# throughhole_xbee.net
KiCad netlist of a schematic drawn in EAGLE
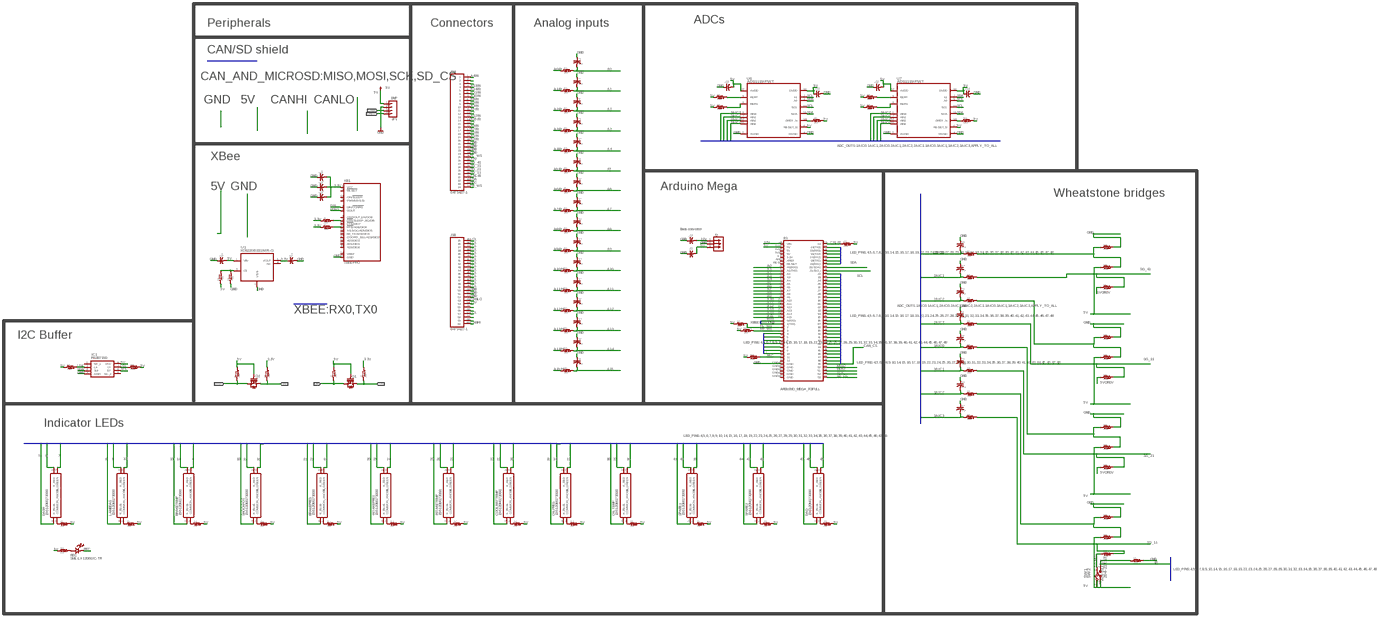
[diagram p0: schematic, sheet 1, overview]
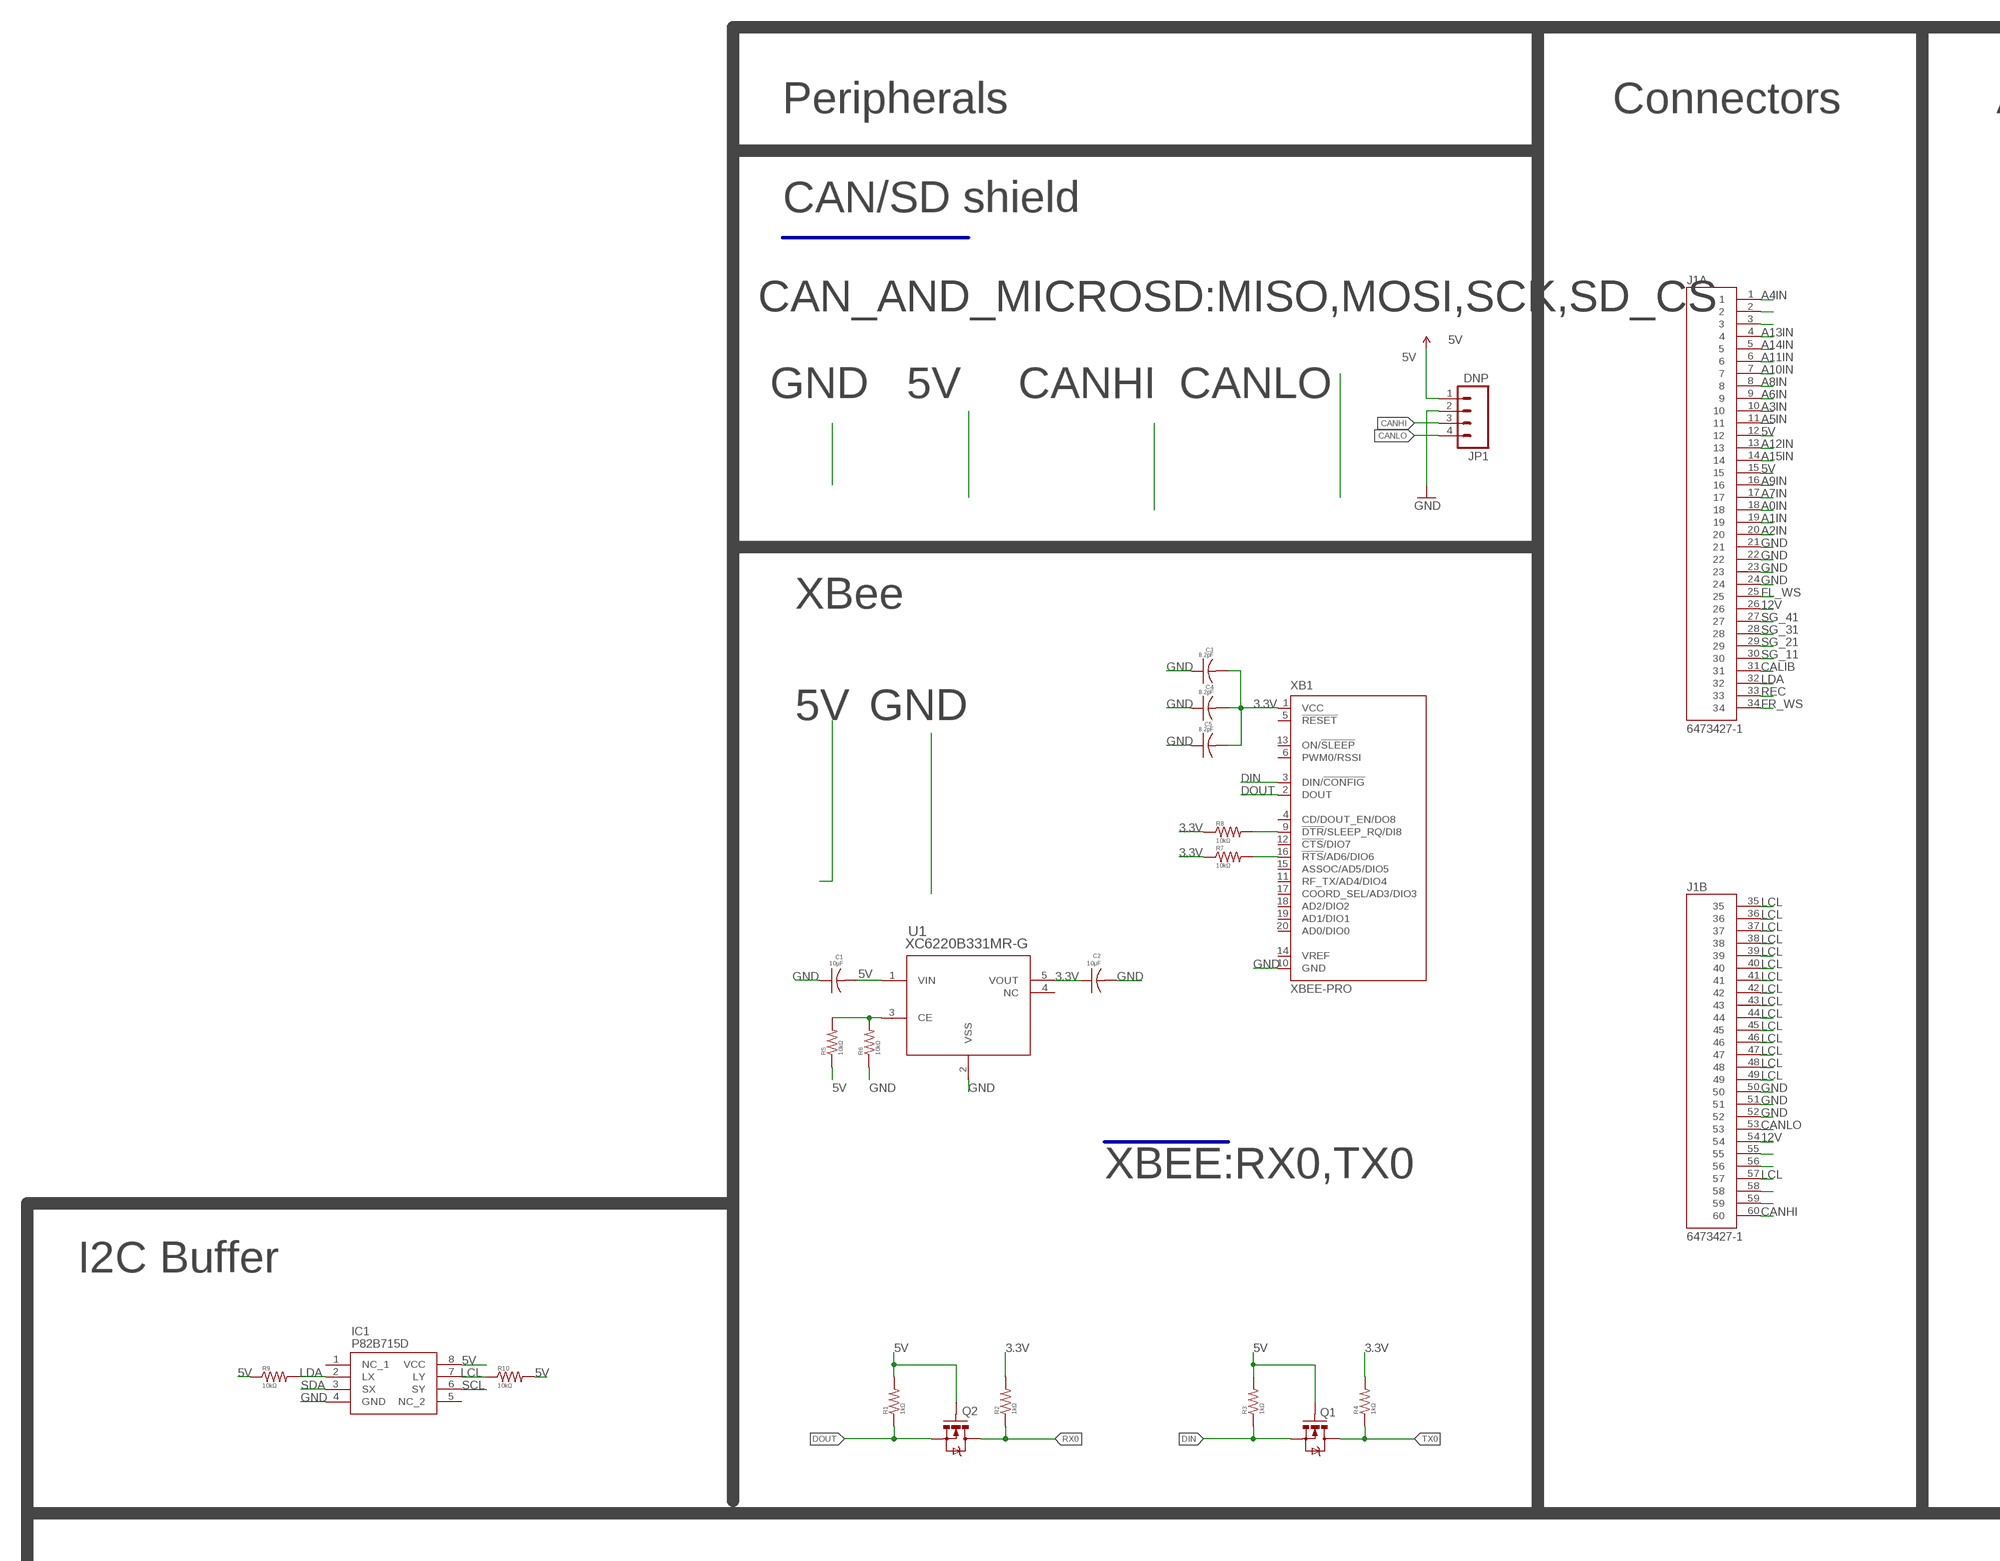
[diagram p1: schematic, sheet 1, part 1 of 5]
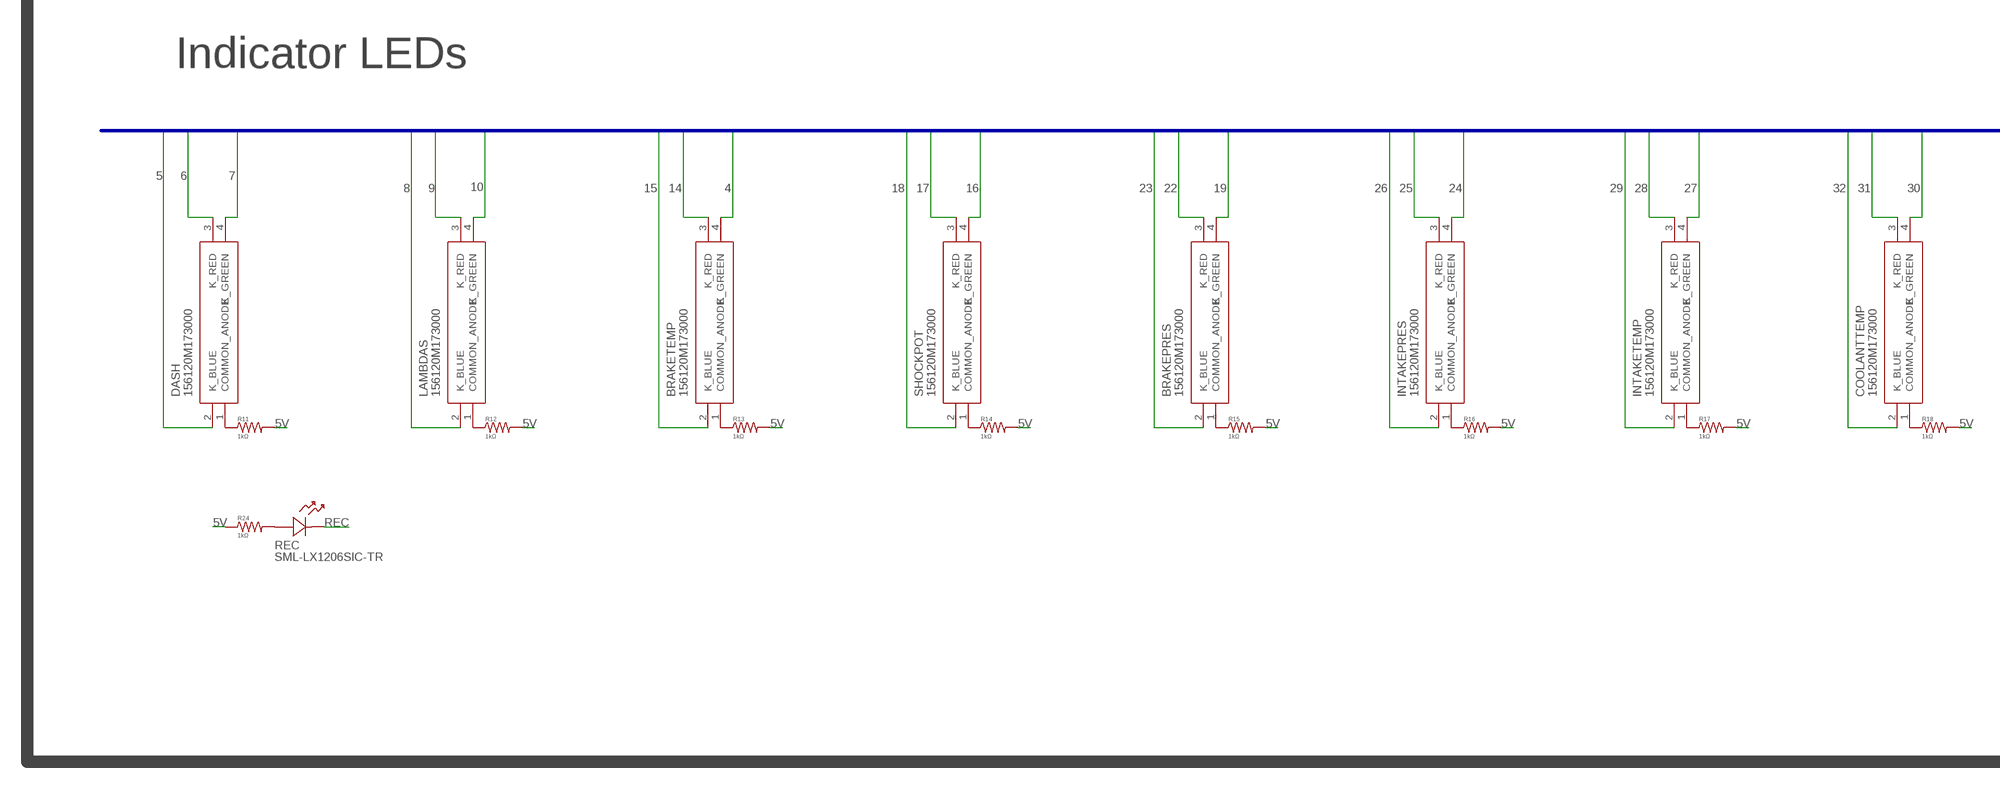
[diagram p2: schematic, sheet 1, part 2 of 5]
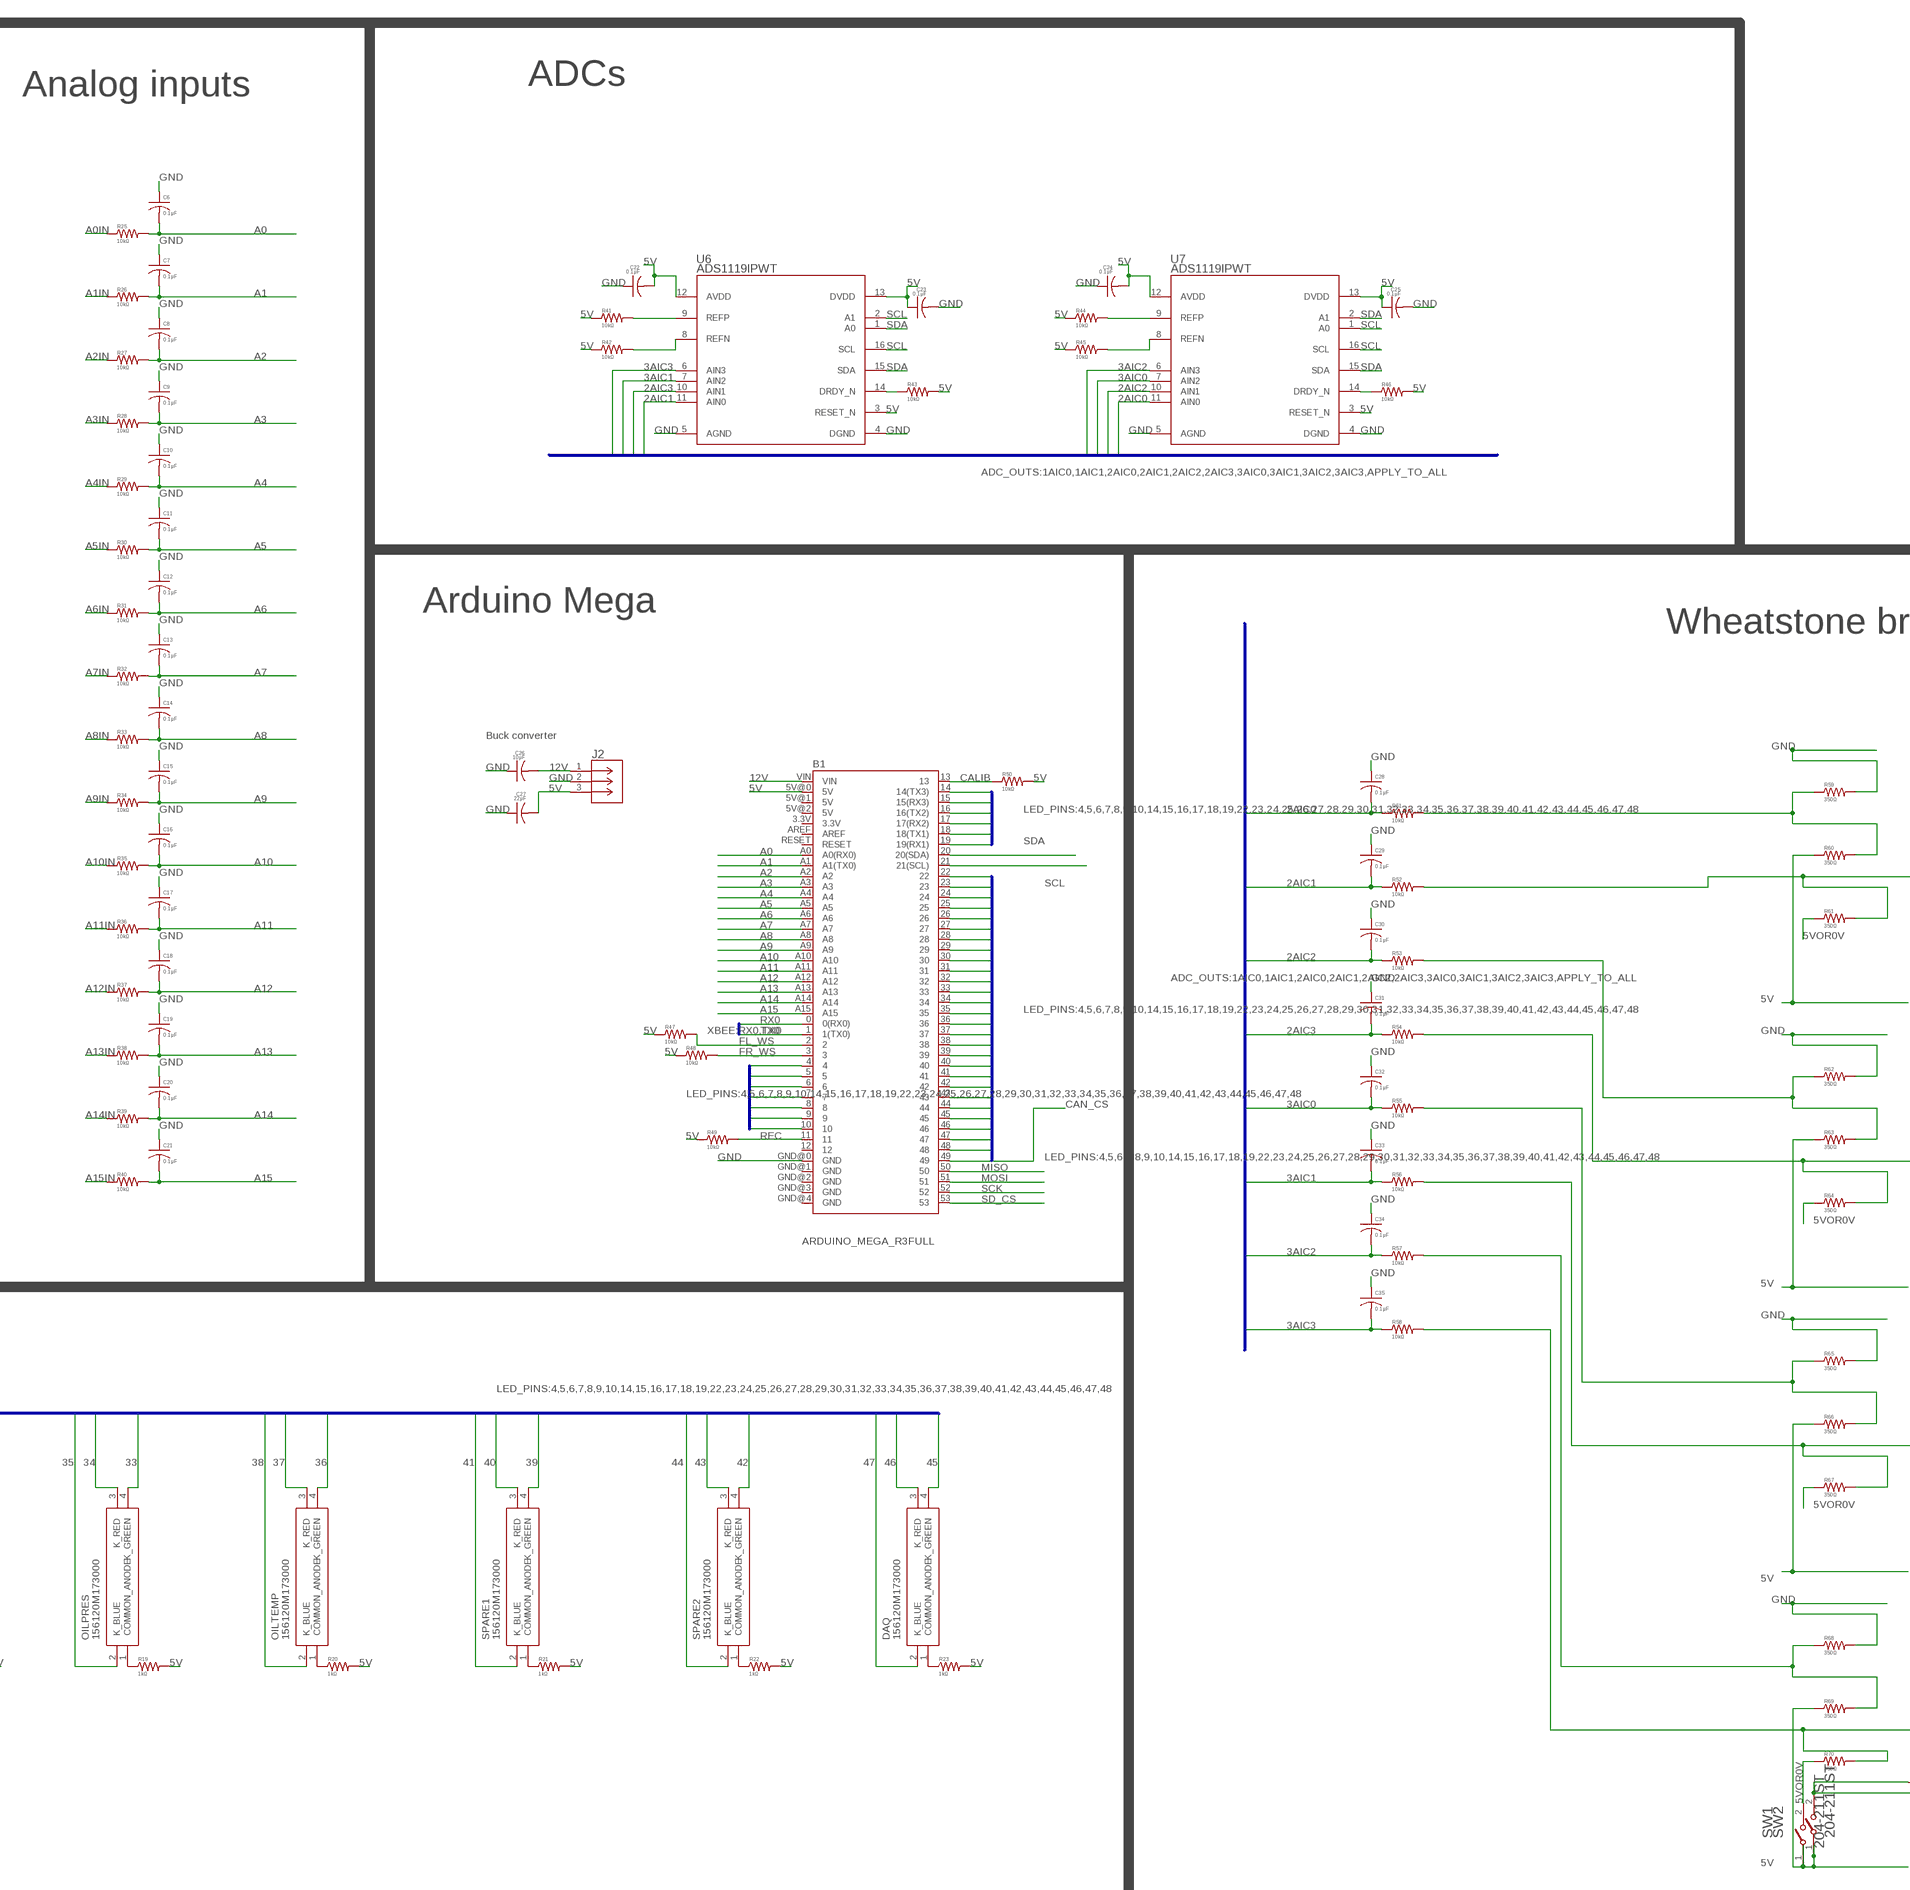
[diagram p3: schematic, sheet 1, part 3 of 5]
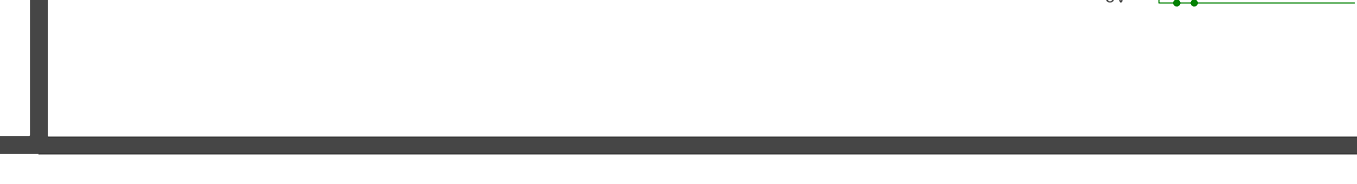
[diagram p4: schematic, sheet 1, part 4 of 5]
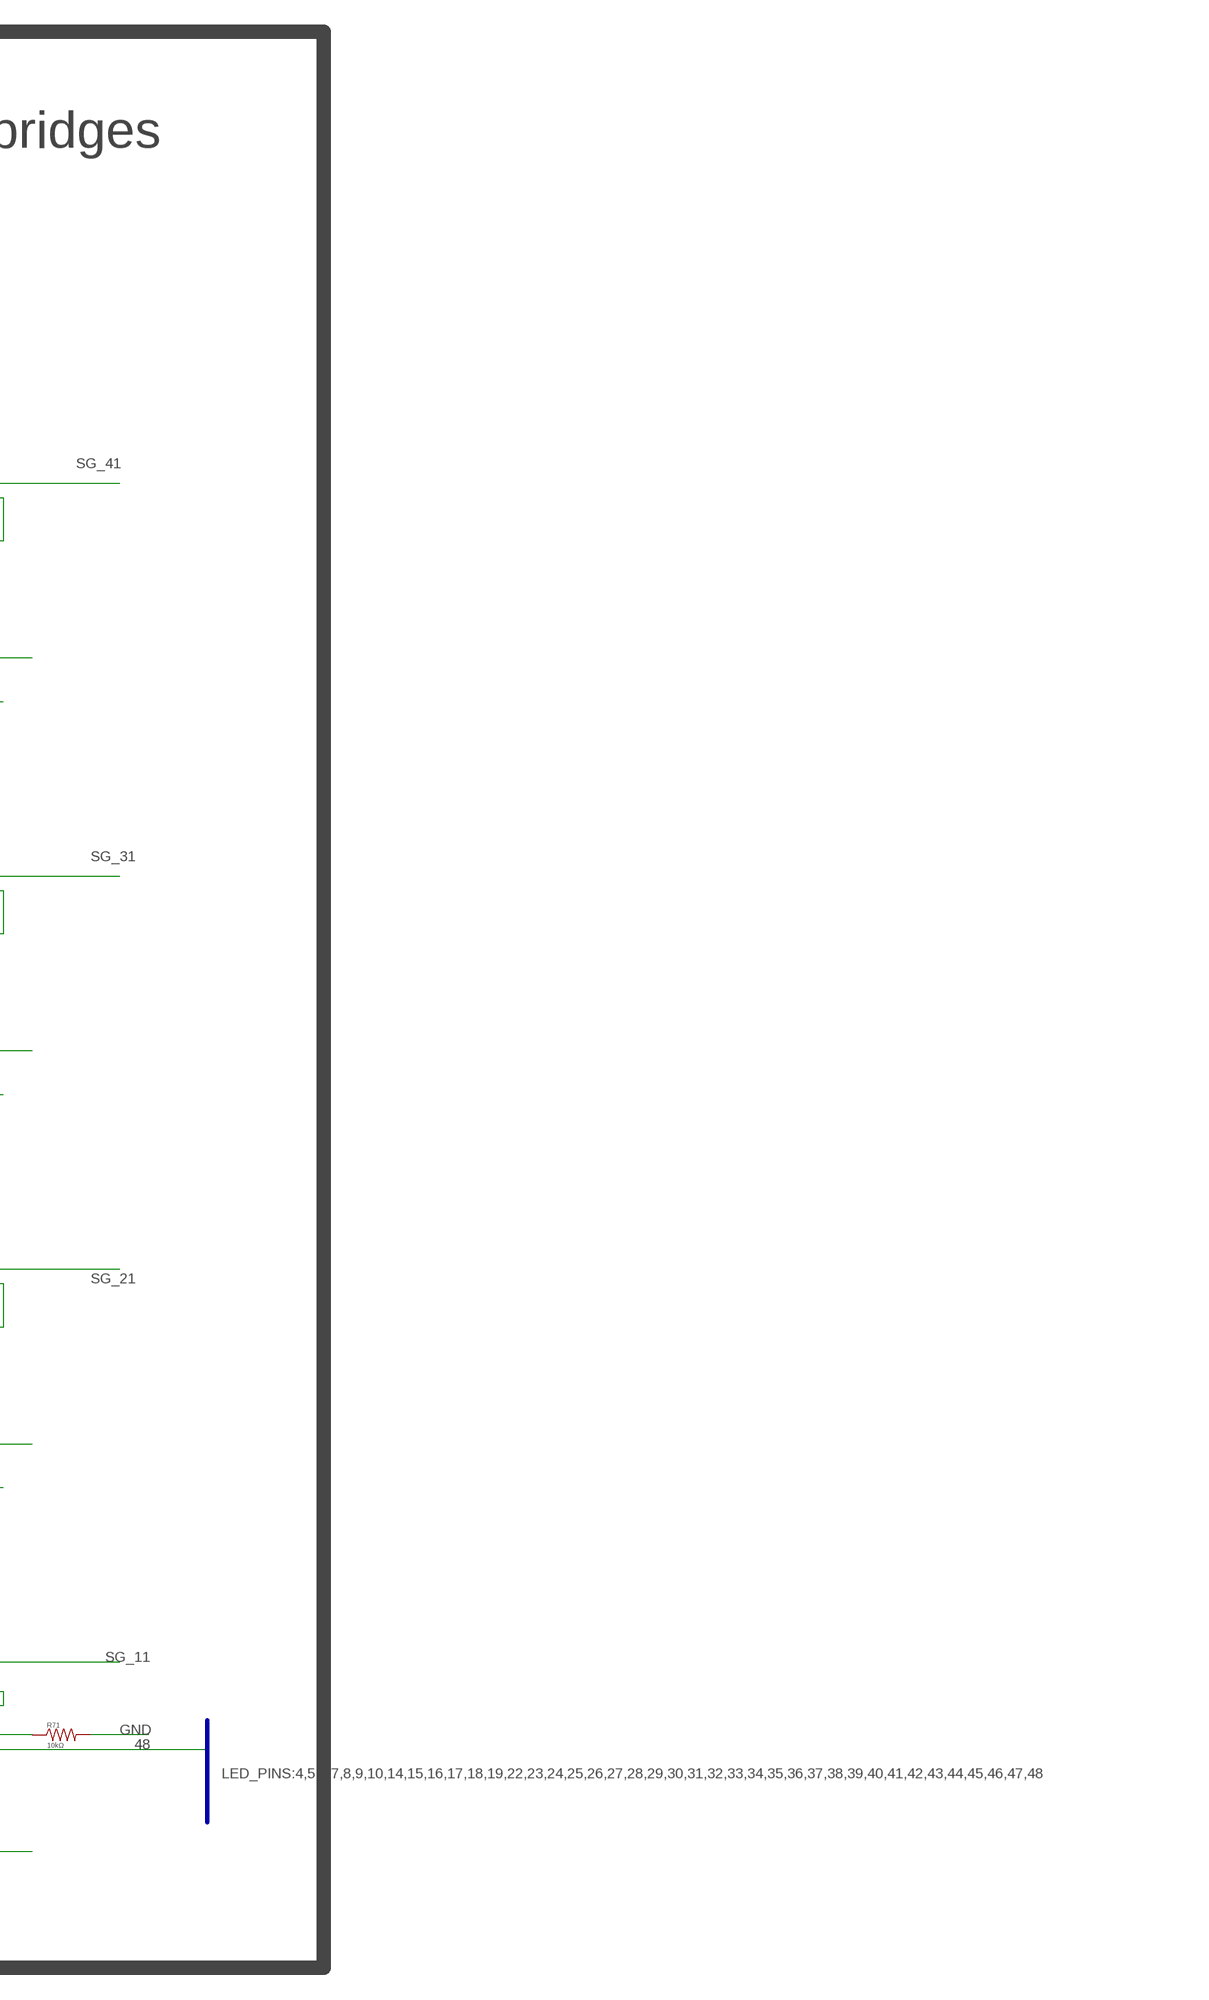
[diagram p5: schematic, sheet 1, part 5 of 5]
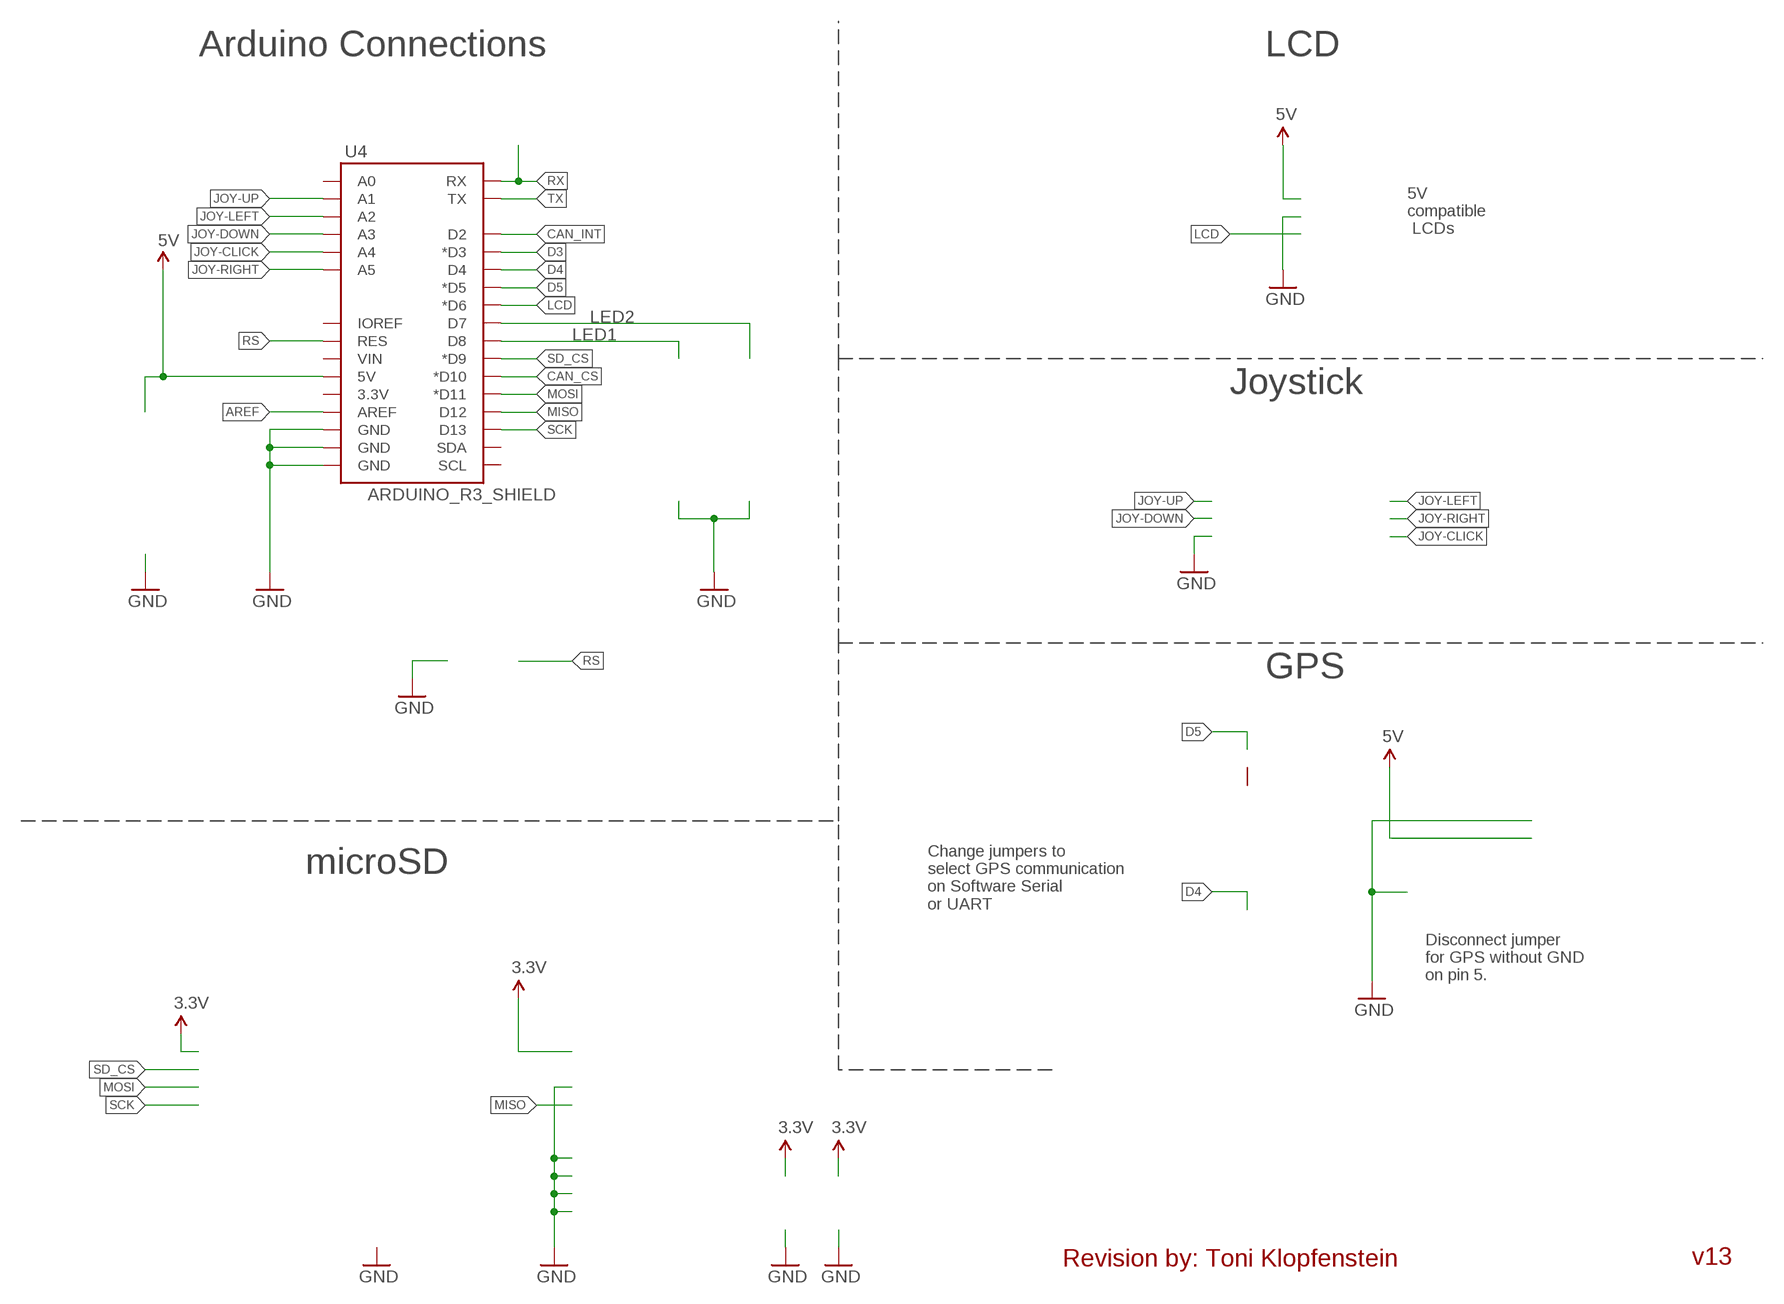
[diagram p6: schematic, sheet 2]

(export (version "E")
  (design (tool "Eeschema 10.0.6"))
  (components
    (comp (ref "U4")
      (value "ARDUINO_R3_SHIELD")
      (footprint "eagle-import:UNO_R3_SHIELD")
      (libsource (lib "eagle-import") (part "ARDUINO_R3_SHIELD"))
    )
    (comp (ref "B1")
      (value "ARDUINO_MEGA_R3FULL")
      (footprint "eagle-import:ARDUINO_MEGA")
      (libsource (lib "eagle-import") (part "ARDUINO_MEGA_R3FULL"))
    )
    (comp (ref "BRAKEPRES")
      (value "156120M173000")
      (footprint "eagle-import:156120M173000")
      (fields (field (name "MOUSER_PART_NUMBER") "710-156120M173000"))
      (libsource (lib "eagle-import") (part "156120M173000"))
    )
    (comp (ref "BRAKETEMP")
      (value "156120M173000")
      (footprint "eagle-import:156120M173000")
      (fields (field (name "MOUSER_PART_NUMBER") "710-156120M173000"))
      (libsource (lib "eagle-import") (part "156120M173000"))
    )
    (comp (ref "C1")
      (value "10μF")
      (footprint "eagle-import:C1206")
      (libsource (lib "eagle-import") (part "C-USC1206"))
    )
    (comp (ref "C2")
      (value "10μF")
      (footprint "eagle-import:C1206")
      (libsource (lib "eagle-import") (part "C-USC1206"))
    )
    (comp (ref "C3")
      (value "8.2pF")
      (footprint "eagle-import:C1206")
      (libsource (lib "eagle-import") (part "C-USC1206"))
    )
    (comp (ref "C4")
      (value "8.2pF")
      (footprint "eagle-import:C1206")
      (libsource (lib "eagle-import") (part "C-USC1206"))
    )
    (comp (ref "C5")
      (value "8.2pF")
      (footprint "eagle-import:C1206")
      (libsource (lib "eagle-import") (part "C-USC1206"))
    )
    (comp (ref "C6")
      (value "0.1μF")
      (footprint "eagle-import:C1206")
      (libsource (lib "eagle-import") (part "C-USC1206"))
    )
    (comp (ref "C7")
      (value "0.1μF")
      (footprint "eagle-import:C1206")
      (libsource (lib "eagle-import") (part "C-USC1206"))
    )
    (comp (ref "C8")
      (value "0.1μF")
      (footprint "eagle-import:C1206")
      (libsource (lib "eagle-import") (part "C-USC1206"))
    )
    (comp (ref "C9")
      (value "0.1μF")
      (footprint "eagle-import:C1206")
      (libsource (lib "eagle-import") (part "C-USC1206"))
    )
    (comp (ref "C10")
      (value "0.1μF")
      (footprint "eagle-import:C1206")
      (libsource (lib "eagle-import") (part "C-USC1206"))
    )
    (comp (ref "C11")
      (value "0.1μF")
      (footprint "eagle-import:C1206")
      (libsource (lib "eagle-import") (part "C-USC1206"))
    )
    (comp (ref "C12")
      (value "0.1μF")
      (footprint "eagle-import:C1206")
      (libsource (lib "eagle-import") (part "C-USC1206"))
    )
    (comp (ref "C13")
      (value "0.1μF")
      (footprint "eagle-import:C1206")
      (libsource (lib "eagle-import") (part "C-USC1206"))
    )
    (comp (ref "C14")
      (value "0.1μF")
      (footprint "eagle-import:C1206")
      (libsource (lib "eagle-import") (part "C-USC1206"))
    )
    (comp (ref "C15")
      (value "0.1μF")
      (footprint "eagle-import:C1206")
      (libsource (lib "eagle-import") (part "C-USC1206"))
    )
    (comp (ref "C16")
      (value "0.1μF")
      (footprint "eagle-import:C1206")
      (libsource (lib "eagle-import") (part "C-USC1206"))
    )
    (comp (ref "C17")
      (value "0.1μF")
      (footprint "eagle-import:C1206")
      (libsource (lib "eagle-import") (part "C-USC1206"))
    )
    (comp (ref "C18")
      (value "0.1μF")
      (footprint "eagle-import:C1206")
      (libsource (lib "eagle-import") (part "C-USC1206"))
    )
    (comp (ref "C19")
      (value "0.1μF")
      (footprint "eagle-import:C1206")
      (libsource (lib "eagle-import") (part "C-USC1206"))
    )
    (comp (ref "C20")
      (value "0.1μF")
      (footprint "eagle-import:C1206")
      (libsource (lib "eagle-import") (part "C-USC1206"))
    )
    (comp (ref "C21")
      (value "0.1μF")
      (footprint "eagle-import:C1206")
      (libsource (lib "eagle-import") (part "C-USC1206"))
    )
    (comp (ref "C22")
      (value "0.1μF")
      (footprint "eagle-import:C1206")
      (libsource (lib "eagle-import") (part "C-USC1206"))
    )
    (comp (ref "C23")
      (value "0.1μF")
      (footprint "eagle-import:C1206")
      (libsource (lib "eagle-import") (part "C-USC1206"))
    )
    (comp (ref "C24")
      (value "0.1μF")
      (footprint "eagle-import:C1206")
      (libsource (lib "eagle-import") (part "C-USC1206"))
    )
    (comp (ref "C25")
      (value "0.1μF")
      (footprint "eagle-import:C1206")
      (libsource (lib "eagle-import") (part "C-USC1206"))
    )
    (comp (ref "C26")
      (value "10μF")
      (footprint "eagle-import:C1206")
      (libsource (lib "eagle-import") (part "C-USC1206"))
    )
    (comp (ref "C27")
      (value "22μF")
      (footprint "eagle-import:C1206")
      (libsource (lib "eagle-import") (part "C-USC1206"))
    )
    (comp (ref "C28")
      (value "0.1μF")
      (footprint "eagle-import:C1206")
      (libsource (lib "eagle-import") (part "C-USC1206"))
    )
    (comp (ref "C29")
      (value "0.1μF")
      (footprint "eagle-import:C1206")
      (libsource (lib "eagle-import") (part "C-USC1206"))
    )
    (comp (ref "C30")
      (value "0.1μF")
      (footprint "eagle-import:C1206")
      (libsource (lib "eagle-import") (part "C-USC1206"))
    )
    (comp (ref "C31")
      (value "0.1μF")
      (footprint "eagle-import:C1206")
      (libsource (lib "eagle-import") (part "C-USC1206"))
    )
    (comp (ref "C32")
      (value "0.1μF")
      (footprint "eagle-import:C1206")
      (libsource (lib "eagle-import") (part "C-USC1206"))
    )
    (comp (ref "C33")
      (value "0.1μF")
      (footprint "eagle-import:C1206")
      (libsource (lib "eagle-import") (part "C-USC1206"))
    )
    (comp (ref "C34")
      (value "0.1μF")
      (footprint "eagle-import:C1206")
      (libsource (lib "eagle-import") (part "C-USC1206"))
    )
    (comp (ref "C35")
      (value "0.1μF")
      (footprint "eagle-import:C1206")
      (libsource (lib "eagle-import") (part "C-USC1206"))
    )
    (comp (ref "COOLANTTEMP")
      (value "156120M173000")
      (footprint "eagle-import:156120M173000")
      (fields (field (name "MOUSER_PART_NUMBER") "710-156120M173000"))
      (libsource (lib "eagle-import") (part "156120M173000"))
    )
    (comp (ref "DAQ")
      (value "156120M173000")
      (footprint "eagle-import:156120M173000")
      (fields (field (name "MOUSER_PART_NUMBER") "710-156120M173000"))
      (libsource (lib "eagle-import") (part "156120M173000"))
    )
    (comp (ref "DASH")
      (value "156120M173000")
      (footprint "eagle-import:156120M173000")
      (fields (field (name "MOUSER_PART_NUMBER") "710-156120M173000"))
      (libsource (lib "eagle-import") (part "156120M173000"))
    )
    (comp (ref "IC1")
      (value "P82B715D")
      (footprint "eagle-import:SOIC127P600X175-8N")
      (fields (field (name "MOUSER_PART_NUMBER") "595-P82B715D"))
      (libsource (lib "eagle-import") (part "P82B715D"))
    )
    (comp (ref "INTAKEPRES")
      (value "156120M173000")
      (footprint "eagle-import:156120M173000")
      (fields (field (name "MOUSER_PART_NUMBER") "710-156120M173000"))
      (libsource (lib "eagle-import") (part "156120M173000"))
    )
    (comp (ref "INTAKETEMP")
      (value "156120M173000")
      (footprint "eagle-import:156120M173000")
      (fields (field (name "MOUSER_PART_NUMBER") "710-156120M173000"))
      (libsource (lib "eagle-import") (part "156120M173000"))
    )
    (comp (ref "J1")
      (value "6473427-1")
      (footprint "eagle-import:TE_6473427-1")
      (fields (field (name "MF") "TE Connectivity"))
      (libsource (lib "eagle-import") (part "6473427-1"))
    )
    (comp (ref "J2")
      (value "VR10S05")
      (footprint "eagle-import:CONN3_10S05_XPP")
      (fields (field (name "COPYRIGHT") "Copyright (C) 2022 Ultra Librarian. All rights reserved."))
      (libsource (lib "eagle-import") (part "VR10S05"))
    )
    (comp (ref "JP1")
      (value "DNP")
      (footprint "eagle-import:1X04")
      (libsource (lib "eagle-import") (part "M04PTH"))
    )
    (comp (ref "LAMBDAS")
      (value "156120M173000")
      (footprint "eagle-import:156120M173000")
      (fields (field (name "MOUSER_PART_NUMBER") "710-156120M173000"))
      (libsource (lib "eagle-import") (part "156120M173000"))
    )
    (comp (ref "OILPRES")
      (value "156120M173000")
      (footprint "eagle-import:156120M173000")
      (fields (field (name "MOUSER_PART_NUMBER") "710-156120M173000"))
      (libsource (lib "eagle-import") (part "156120M173000"))
    )
    (comp (ref "OILTEMP")
      (value "156120M173000")
      (footprint "eagle-import:156120M173000")
      (fields (field (name "MOUSER_PART_NUMBER") "710-156120M173000"))
      (libsource (lib "eagle-import") (part "156120M173000"))
    )
    (comp (ref "Q1")
      (value "MOSFET-NCHANNELSMD")
      (footprint "eagle-import:SOT23-3")
      (libsource (lib "eagle-import") (part "MOSFET-NCHANNELSMD"))
    )
    (comp (ref "Q2")
      (value "MOSFET-NCHANNELSMD")
      (footprint "eagle-import:SOT23-3")
      (libsource (lib "eagle-import") (part "MOSFET-NCHANNELSMD"))
    )
    (comp (ref "R1")
      (value "1kΩ")
      (footprint "eagle-import:R1206")
      (libsource (lib "eagle-import") (part "R-US_R1206"))
    )
    (comp (ref "R2")
      (value "1kΩ")
      (footprint "eagle-import:R1206")
      (libsource (lib "eagle-import") (part "R-US_R1206"))
    )
    (comp (ref "R3")
      (value "1kΩ")
      (footprint "eagle-import:R1206")
      (libsource (lib "eagle-import") (part "R-US_R1206"))
    )
    (comp (ref "R4")
      (value "1kΩ")
      (footprint "eagle-import:R1206")
      (libsource (lib "eagle-import") (part "R-US_R1206"))
    )
    (comp (ref "R5")
      (value "10kΩ")
      (footprint "eagle-import:R1206")
      (libsource (lib "eagle-import") (part "R-US_R1206"))
    )
    (comp (ref "R6")
      (value "10kΩ")
      (footprint "eagle-import:R1206")
      (libsource (lib "eagle-import") (part "R-US_R1206"))
    )
    (comp (ref "R7")
      (value "10kΩ")
      (footprint "eagle-import:R1206")
      (libsource (lib "eagle-import") (part "R-US_R1206"))
    )
    (comp (ref "R8")
      (value "10kΩ")
      (footprint "eagle-import:R1206")
      (libsource (lib "eagle-import") (part "R-US_R1206"))
    )
    (comp (ref "R9")
      (value "10kΩ")
      (footprint "eagle-import:R1206")
      (libsource (lib "eagle-import") (part "R-US_R1206"))
    )
    (comp (ref "R10")
      (value "10kΩ")
      (footprint "eagle-import:R1206")
      (libsource (lib "eagle-import") (part "R-US_R1206"))
    )
    (comp (ref "R11")
      (value "1kΩ")
      (footprint "eagle-import:R1206")
      (libsource (lib "eagle-import") (part "R-US_R1206"))
    )
    (comp (ref "R12")
      (value "1kΩ")
      (footprint "eagle-import:R1206")
      (libsource (lib "eagle-import") (part "R-US_R1206"))
    )
    (comp (ref "R13")
      (value "1kΩ")
      (footprint "eagle-import:R1206")
      (libsource (lib "eagle-import") (part "R-US_R1206"))
    )
    (comp (ref "R14")
      (value "1kΩ")
      (footprint "eagle-import:R1206")
      (libsource (lib "eagle-import") (part "R-US_R1206"))
    )
    (comp (ref "R15")
      (value "1kΩ")
      (footprint "eagle-import:R1206")
      (libsource (lib "eagle-import") (part "R-US_R1206"))
    )
    (comp (ref "R16")
      (value "1kΩ")
      (footprint "eagle-import:R1206")
      (libsource (lib "eagle-import") (part "R-US_R1206"))
    )
    (comp (ref "R17")
      (value "1kΩ")
      (footprint "eagle-import:R1206")
      (libsource (lib "eagle-import") (part "R-US_R1206"))
    )
    (comp (ref "R18")
      (value "1kΩ")
      (footprint "eagle-import:R1206")
      (libsource (lib "eagle-import") (part "R-US_R1206"))
    )
    (comp (ref "R19")
      (value "1kΩ")
      (footprint "eagle-import:R1206")
      (libsource (lib "eagle-import") (part "R-US_R1206"))
    )
    (comp (ref "R20")
      (value "1kΩ")
      (footprint "eagle-import:R1206")
      (libsource (lib "eagle-import") (part "R-US_R1206"))
    )
    (comp (ref "R21")
      (value "1kΩ")
      (footprint "eagle-import:R1206")
      (libsource (lib "eagle-import") (part "R-US_R1206"))
    )
    (comp (ref "R22")
      (value "1kΩ")
      (footprint "eagle-import:R1206")
      (libsource (lib "eagle-import") (part "R-US_R1206"))
    )
    (comp (ref "R23")
      (value "1kΩ")
      (footprint "eagle-import:R1206")
      (libsource (lib "eagle-import") (part "R-US_R1206"))
    )
    (comp (ref "R24")
      (value "1kΩ")
      (footprint "eagle-import:R1206")
      (libsource (lib "eagle-import") (part "R-US_R1206"))
    )
    (comp (ref "R25")
      (value "10kΩ")
      (footprint "eagle-import:R1206")
      (libsource (lib "eagle-import") (part "R-US_R1206"))
    )
    (comp (ref "R26")
      (value "10kΩ")
      (footprint "eagle-import:R1206")
      (libsource (lib "eagle-import") (part "R-US_R1206"))
    )
    (comp (ref "R27")
      (value "10kΩ")
      (footprint "eagle-import:R1206")
      (libsource (lib "eagle-import") (part "R-US_R1206"))
    )
    (comp (ref "R28")
      (value "10kΩ")
      (footprint "eagle-import:R1206")
      (libsource (lib "eagle-import") (part "R-US_R1206"))
    )
    (comp (ref "R29")
      (value "10kΩ")
      (footprint "eagle-import:R1206")
      (libsource (lib "eagle-import") (part "R-US_R1206"))
    )
    (comp (ref "R30")
      (value "10kΩ")
      (footprint "eagle-import:R1206")
      (libsource (lib "eagle-import") (part "R-US_R1206"))
    )
    (comp (ref "R31")
      (value "10kΩ")
      (footprint "eagle-import:R1206")
      (libsource (lib "eagle-import") (part "R-US_R1206"))
    )
    (comp (ref "R32")
      (value "10kΩ")
      (footprint "eagle-import:R1206")
      (libsource (lib "eagle-import") (part "R-US_R1206"))
    )
    (comp (ref "R33")
      (value "10kΩ")
      (footprint "eagle-import:R1206")
      (libsource (lib "eagle-import") (part "R-US_R1206"))
    )
    (comp (ref "R34")
      (value "10kΩ")
      (footprint "eagle-import:R1206")
      (libsource (lib "eagle-import") (part "R-US_R1206"))
    )
    (comp (ref "R35")
      (value "10kΩ")
      (footprint "eagle-import:R1206")
      (libsource (lib "eagle-import") (part "R-US_R1206"))
    )
    (comp (ref "R36")
      (value "10kΩ")
      (footprint "eagle-import:R1206")
      (libsource (lib "eagle-import") (part "R-US_R1206"))
    )
    (comp (ref "R37")
      (value "10kΩ")
      (footprint "eagle-import:R1206")
      (libsource (lib "eagle-import") (part "R-US_R1206"))
    )
    (comp (ref "R38")
      (value "10kΩ")
      (footprint "eagle-import:R1206")
      (libsource (lib "eagle-import") (part "R-US_R1206"))
    )
    (comp (ref "R39")
      (value "10kΩ")
      (footprint "eagle-import:R1206")
      (libsource (lib "eagle-import") (part "R-US_R1206"))
    )
    (comp (ref "R40")
      (value "10kΩ")
      (footprint "eagle-import:R1206")
      (libsource (lib "eagle-import") (part "R-US_R1206"))
    )
    (comp (ref "R41")
      (value "10kΩ")
      (footprint "eagle-import:R1206")
      (libsource (lib "eagle-import") (part "R-US_R1206"))
    )
    (comp (ref "R42")
      (value "10kΩ")
      (footprint "eagle-import:R1206")
      (libsource (lib "eagle-import") (part "R-US_R1206"))
    )
    (comp (ref "R43")
      (value "10kΩ")
      (footprint "eagle-import:R1206")
      (libsource (lib "eagle-import") (part "R-US_R1206"))
    )
    (comp (ref "R44")
      (value "10kΩ")
      (footprint "eagle-import:R1206")
      (libsource (lib "eagle-import") (part "R-US_R1206"))
    )
    (comp (ref "R45")
      (value "10kΩ")
      (footprint "eagle-import:R1206")
      (libsource (lib "eagle-import") (part "R-US_R1206"))
    )
    (comp (ref "R46")
      (value "10kΩ")
      (footprint "eagle-import:R1206")
      (libsource (lib "eagle-import") (part "R-US_R1206"))
    )
    (comp (ref "R47")
      (value "10kΩ")
      (footprint "eagle-import:R1206")
      (libsource (lib "eagle-import") (part "R-US_R1206"))
    )
    (comp (ref "R48")
      (value "10kΩ")
      (footprint "eagle-import:R1206")
      (libsource (lib "eagle-import") (part "R-US_R1206"))
    )
    (comp (ref "R49")
      (value "10kΩ")
      (footprint "eagle-import:R1206")
      (libsource (lib "eagle-import") (part "R-US_R1206"))
    )
    (comp (ref "R50")
      (value "10kΩ")
      (footprint "eagle-import:R1206")
      (libsource (lib "eagle-import") (part "R-US_R1206"))
    )
    (comp (ref "R51")
      (value "10kΩ")
      (footprint "eagle-import:R1206")
      (libsource (lib "eagle-import") (part "R-US_R1206"))
    )
    (comp (ref "R52")
      (value "10kΩ")
      (footprint "eagle-import:R1206")
      (libsource (lib "eagle-import") (part "R-US_R1206"))
    )
    (comp (ref "R53")
      (value "10kΩ")
      (footprint "eagle-import:R1206")
      (libsource (lib "eagle-import") (part "R-US_R1206"))
    )
    (comp (ref "R54")
      (value "10kΩ")
      (footprint "eagle-import:R1206")
      (libsource (lib "eagle-import") (part "R-US_R1206"))
    )
    (comp (ref "R55")
      (value "10kΩ")
      (footprint "eagle-import:R1206")
      (libsource (lib "eagle-import") (part "R-US_R1206"))
    )
    (comp (ref "R56")
      (value "10kΩ")
      (footprint "eagle-import:R1206")
      (libsource (lib "eagle-import") (part "R-US_R1206"))
    )
    (comp (ref "R57")
      (value "10kΩ")
      (footprint "eagle-import:R1206")
      (libsource (lib "eagle-import") (part "R-US_R1206"))
    )
    (comp (ref "R58")
      (value "10kΩ")
      (footprint "eagle-import:R1206")
      (libsource (lib "eagle-import") (part "R-US_R1206"))
    )
    (comp (ref "R59")
      (value "350Ω")
      (footprint "eagle-import:R1206")
      (libsource (lib "eagle-import") (part "R-US_R1206"))
    )
    (comp (ref "R60")
      (value "350Ω")
      (footprint "eagle-import:R1206")
      (libsource (lib "eagle-import") (part "R-US_R1206"))
    )
    (comp (ref "R61")
      (value "350Ω")
      (footprint "eagle-import:R1206")
      (libsource (lib "eagle-import") (part "R-US_R1206"))
    )
    (comp (ref "R62")
      (value "350Ω")
      (footprint "eagle-import:R1206")
      (libsource (lib "eagle-import") (part "R-US_R1206"))
    )
    (comp (ref "R63")
      (value "350Ω")
      (footprint "eagle-import:R1206")
      (libsource (lib "eagle-import") (part "R-US_R1206"))
    )
    (comp (ref "R64")
      (value "350Ω")
      (footprint "eagle-import:R1206")
      (libsource (lib "eagle-import") (part "R-US_R1206"))
    )
    (comp (ref "R65")
      (value "350Ω")
      (footprint "eagle-import:R1206")
      (libsource (lib "eagle-import") (part "R-US_R1206"))
    )
    (comp (ref "R66")
      (value "350Ω")
      (footprint "eagle-import:R1206")
      (libsource (lib "eagle-import") (part "R-US_R1206"))
    )
    (comp (ref "R67")
      (value "350Ω")
      (footprint "eagle-import:R1206")
      (libsource (lib "eagle-import") (part "R-US_R1206"))
    )
    (comp (ref "R68")
      (value "350Ω")
      (footprint "eagle-import:R1206")
      (libsource (lib "eagle-import") (part "R-US_R1206"))
    )
    (comp (ref "R69")
      (value "350Ω")
      (footprint "eagle-import:R1206")
      (libsource (lib "eagle-import") (part "R-US_R1206"))
    )
    (comp (ref "R70")
      (value "350Ω")
      (footprint "eagle-import:R1206")
      (libsource (lib "eagle-import") (part "R-US_R1206"))
    )
    (comp (ref "R71")
      (value "10kΩ")
      (footprint "eagle-import:R1206")
      (libsource (lib "eagle-import") (part "R-US_R1206"))
    )
    (comp (ref "REC")
      (value "SML-LX1206SIC-TR")
      (footprint "eagle-import:LED_SML-LX1206SIC-TR_LUM")
      (fields (field (name "COPYRIGHT") "Copyright (C) 2021 Ultra Librarian. All rights reserved."))
      (libsource (lib "eagle-import") (part "SML-LX1206SIC-TR"))
    )
    (comp (ref "SHOCKPOT")
      (value "156120M173000")
      (footprint "eagle-import:156120M173000")
      (fields (field (name "MOUSER_PART_NUMBER") "710-156120M173000"))
      (libsource (lib "eagle-import") (part "156120M173000"))
    )
    (comp (ref "SPARE1")
      (value "156120M173000")
      (footprint "eagle-import:156120M173000")
      (fields (field (name "MOUSER_PART_NUMBER") "710-156120M173000"))
      (libsource (lib "eagle-import") (part "156120M173000"))
    )
    (comp (ref "SPARE2")
      (value "156120M173000")
      (footprint "eagle-import:156120M173000")
      (fields (field (name "MOUSER_PART_NUMBER") "710-156120M173000"))
      (libsource (lib "eagle-import") (part "156120M173000"))
    )
    (comp (ref "SW1")
      (value "CTS_ELECTROCOMPONENTS_204-211STCTS_ELECTROCOMPONENTS_204-211ST_0_0")
      (footprint "eagle-import:CTS_ELECTROCOMPONENTS_204-211ST_0")
      (fields
        (field (name "DIGIKEY_PART_NUMBER") "CT3103CT-ND")
        (field (name "MF") "CTS Electrocomponents")
        (field (name "MOUSER_PART_NUMBER") "774-204-211STR")
      )
      (libsource (lib "eagle-import") (part "CTS_ELECTROCOMPONENTS_204-211STCTS_ELECTROCOMPONENTS_204-211ST_0_0"))
    )
    (comp (ref "SW2")
      (value "CTS_ELECTROCOMPONENTS_204-211STCTS_ELECTROCOMPONENTS_204-211ST_0_0")
      (footprint "eagle-import:CTS_ELECTROCOMPONENTS_204-211ST_0")
      (fields
        (field (name "DIGIKEY_PART_NUMBER") "CT3103CT-ND")
        (field (name "MF") "CTS Electrocomponents")
        (field (name "MOUSER_PART_NUMBER") "774-204-211STR")
      )
      (libsource (lib "eagle-import") (part "CTS_ELECTROCOMPONENTS_204-211STCTS_ELECTROCOMPONENTS_204-211ST_0_0"))
    )
    (comp (ref "U1")
      (value "XC6220B331MR-G")
      (footprint "eagle-import:SOT-25_TOR")
      (fields (field (name "COPYRIGHT") "Copyright (C) 2022 Ultra Librarian. All rights reserved."))
      (libsource (lib "eagle-import") (part "XC6220B331MR-G"))
    )
    (comp (ref "U6")
      (value "ADS1119IPWT")
      (footprint "eagle-import:PW0016A_N")
      (fields (field (name "COPYRIGHT") "Copyright (C) 2021 Ultra Librarian. All rights reserved."))
      (libsource (lib "eagle-import") (part "ADS1119IPWT"))
    )
    (comp (ref "U7")
      (value "ADS1119IPWT")
      (footprint "eagle-import:PW0016A_N")
      (fields (field (name "COPYRIGHT") "Copyright (C) 2021 Ultra Librarian. All rights reserved."))
      (libsource (lib "eagle-import") (part "ADS1119IPWT"))
    )
    (comp (ref "XB1")
      (value "XBEE-PRO")
      (footprint "eagle-import:XBEE-PRO")
      (fields (field (name "MPN") "XBP24-AWI-001"))
      (libsource (lib "eagle-import") (part "XBEE-PRO"))
    )
  )
  (nets
    (net (code "11") (name "2AIC0") (class "Default")
      (node (ref "C28") (pin "2") (pinfunction "2_2") (pintype "passive"))
      (node (ref "R51") (pin "1") (pinfunction "1_1") (pintype "passive"))
      (node (ref "U7") (pin "11") (pinfunction "AIN0_11") (pintype "input"))
    )
    (net (code "12") (name "2AIC1") (class "Default")
      (node (ref "C29") (pin "2") (pinfunction "2_2") (pintype "passive"))
      (node (ref "R52") (pin "1") (pinfunction "1_1") (pintype "passive"))
      (node (ref "U6") (pin "11") (pinfunction "AIN0_11") (pintype "input"))
    )
    (net (code "13") (name "2AIC2") (class "Default")
      (node (ref "C30") (pin "2") (pinfunction "2_2") (pintype "passive"))
      (node (ref "R53") (pin "1") (pinfunction "1_1") (pintype "passive"))
      (node (ref "U7") (pin "10") (pinfunction "AIN1_10") (pintype "input"))
    )
    (net (code "14") (name "2AIC3") (class "Default")
      (node (ref "C31") (pin "2") (pinfunction "2_2") (pintype "passive"))
      (node (ref "R54") (pin "1") (pinfunction "1_1") (pintype "passive"))
      (node (ref "U6") (pin "10") (pinfunction "AIN1_10") (pintype "input"))
    )
    (net (code "15") (name "3.3V") (class "Default")
      (node (ref "C2") (pin "1") (pinfunction "1_1") (pintype "passive"))
      (node (ref "C3") (pin "2") (pinfunction "2_2") (pintype "passive"))
      (node (ref "C4") (pin "2") (pinfunction "2_2") (pintype "passive"))
      (node (ref "C5") (pin "2") (pinfunction "2_2") (pintype "passive"))
      (node (ref "R2") (pin "2") (pinfunction "2_2") (pintype "passive"))
      (node (ref "R4") (pin "2") (pinfunction "2_2") (pintype "passive"))
      (node (ref "R7") (pin "1") (pinfunction "1_1") (pintype "passive"))
      (node (ref "R8") (pin "1") (pinfunction "1_1") (pintype "passive"))
      (node (ref "U1") (pin "5") (pinfunction "VOUT_5") (pintype "output"))
      (node (ref "XB1") (pin "1") (pinfunction "VCC_1") (pintype "power_in"))
    )
    (net (code "16") (name "3AIC0") (class "Default")
      (node (ref "C32") (pin "2") (pinfunction "2_2") (pintype "passive"))
      (node (ref "R55") (pin "1") (pinfunction "1_1") (pintype "passive"))
      (node (ref "U7") (pin "7") (pinfunction "AIN2_7") (pintype "input"))
    )
    (net (code "17") (name "3AIC1") (class "Default")
      (node (ref "C33") (pin "2") (pinfunction "2_2") (pintype "passive"))
      (node (ref "R56") (pin "1") (pinfunction "1_1") (pintype "passive"))
      (node (ref "U6") (pin "7") (pinfunction "AIN2_7") (pintype "input"))
    )
    (net (code "18") (name "3AIC2") (class "Default")
      (node (ref "C34") (pin "2") (pinfunction "2_2") (pintype "passive"))
      (node (ref "R57") (pin "1") (pinfunction "1_1") (pintype "passive"))
      (node (ref "U7") (pin "6") (pinfunction "AIN3_6") (pintype "input"))
    )
    (net (code "19") (name "3AIC3") (class "Default")
      (node (ref "C35") (pin "2") (pinfunction "2_2") (pintype "passive"))
      (node (ref "R58") (pin "1") (pinfunction "1_1") (pintype "passive"))
      (node (ref "U6") (pin "6") (pinfunction "AIN3_6") (pintype "input"))
    )
    (net (code "20") (name "4") (class "Default")
      (node (ref "B1") (pin "4") (pinfunction "4_4") (pintype "bidirectional"))
      (node (ref "BRAKETEMP") (pin "4") (pinfunction "K_GREEN_4") (pintype "bidirectional"))
    )
    (net (code "21") (name "5") (class "Default")
      (node (ref "B1") (pin "5") (pinfunction "5_5") (pintype "bidirectional"))
      (node (ref "DASH") (pin "2") (pinfunction "K_BLUE_2") (pintype "bidirectional"))
    )
    (net (code "22") (name "5V") (class "Default")
      (node (ref "B1") (pin "5V@0") (pinfunction "5V_5V@0") (pintype "bidirectional"))
      (node (ref "C1") (pin "2") (pinfunction "2_2") (pintype "passive"))
      (node (ref "C22") (pin "2") (pinfunction "2_2") (pintype "passive"))
      (node (ref "C23") (pin "1") (pinfunction "1_1") (pintype "passive"))
      (node (ref "C24") (pin "2") (pinfunction "2_2") (pintype "passive"))
      (node (ref "C25") (pin "1") (pinfunction "1_1") (pintype "passive"))
      (node (ref "C27") (pin "2") (pinfunction "2_2") (pintype "passive"))
      (node (ref "IC1") (pin "8") (pinfunction "VCC_8") (pintype "bidirectional"))
      (node (ref "J1") (pin "12") (pinfunction "12_12") (pintype "passive"))
      (node (ref "J1") (pin "15") (pinfunction "15_15") (pintype "passive"))
      (node (ref "J2") (pin "3") (pinfunction "3_3") (pintype "passive"))
      (node (ref "JP1") (pin "1") (pinfunction "1_1") (pintype "passive"))
      (node (ref "Q1") (pin "1") (pinfunction "G_1") (pintype "passive"))
      (node (ref "Q2") (pin "1") (pinfunction "G_1") (pintype "passive"))
      (node (ref "R1") (pin "2") (pinfunction "2_2") (pintype "passive"))
      (node (ref "R10") (pin "2") (pinfunction "2_2") (pintype "passive"))
      (node (ref "R11") (pin "2") (pinfunction "2_2") (pintype "passive"))
      (node (ref "R12") (pin "2") (pinfunction "2_2") (pintype "passive"))
      (node (ref "R13") (pin "2") (pinfunction "2_2") (pintype "passive"))
      (node (ref "R14") (pin "2") (pinfunction "2_2") (pintype "passive"))
      (node (ref "R15") (pin "2") (pinfunction "2_2") (pintype "passive"))
      (node (ref "R16") (pin "2") (pinfunction "2_2") (pintype "passive"))
      (node (ref "R17") (pin "2") (pinfunction "2_2") (pintype "passive"))
      (node (ref "R18") (pin "2") (pinfunction "2_2") (pintype "passive"))
      (node (ref "R19") (pin "2") (pinfunction "2_2") (pintype "passive"))
      (node (ref "R20") (pin "2") (pinfunction "2_2") (pintype "passive"))
      (node (ref "R21") (pin "2") (pinfunction "2_2") (pintype "passive"))
      (node (ref "R22") (pin "2") (pinfunction "2_2") (pintype "passive"))
      (node (ref "R23") (pin "2") (pinfunction "2_2") (pintype "passive"))
      (node (ref "R24") (pin "1") (pinfunction "1_1") (pintype "passive"))
      (node (ref "R3") (pin "2") (pinfunction "2_2") (pintype "passive"))
      (node (ref "R41") (pin "1") (pinfunction "1_1") (pintype "passive"))
      (node (ref "R42") (pin "1") (pinfunction "1_1") (pintype "passive"))
      (node (ref "R43") (pin "2") (pinfunction "2_2") (pintype "passive"))
      (node (ref "R44") (pin "1") (pinfunction "1_1") (pintype "passive"))
      (node (ref "R45") (pin "1") (pinfunction "1_1") (pintype "passive"))
      (node (ref "R46") (pin "2") (pinfunction "2_2") (pintype "passive"))
      (node (ref "R47") (pin "1") (pinfunction "1_1") (pintype "passive"))
      (node (ref "R48") (pin "1") (pinfunction "1_1") (pintype "passive"))
      (node (ref "R49") (pin "1") (pinfunction "1_1") (pintype "passive"))
      (node (ref "R5") (pin "1") (pinfunction "1_1") (pintype "passive"))
      (node (ref "R50") (pin "2") (pinfunction "2_2") (pintype "passive"))
      (node (ref "R60") (pin "1") (pinfunction "1_1") (pintype "passive"))
      (node (ref "R63") (pin "1") (pinfunction "1_1") (pintype "passive"))
      (node (ref "R66") (pin "1") (pinfunction "1_1") (pintype "passive"))
      (node (ref "R69") (pin "1") (pinfunction "1_1") (pintype "passive"))
      (node (ref "R9") (pin "1") (pinfunction "1_1") (pintype "passive"))
      (node (ref "SW1") (pin "1") (pinfunction "1_1") (pintype "passive"))
      (node (ref "SW2") (pin "1") (pinfunction "1_1") (pintype "passive"))
      (node (ref "U1") (pin "1") (pinfunction "VIN_1") (pintype "power_in"))
      (node (ref "U4") (pin "5V") (pinfunction "5V_5V") (pintype "bidirectional"))
      (node (ref "U6") (pin "12") (pinfunction "AVDD_12") (pintype "power_in"))
      (node (ref "U6") (pin "13") (pinfunction "DVDD_13") (pintype "power_in"))
      (node (ref "U6") (pin "3") (pinfunction "RESET_N_3") (pintype "input"))
      (node (ref "U7") (pin "12") (pinfunction "AVDD_12") (pintype "power_in"))
      (node (ref "U7") (pin "13") (pinfunction "DVDD_13") (pintype "power_in"))
      (node (ref "U7") (pin "3") (pinfunction "RESET_N_3") (pintype "input"))
    )
    (net (code "23") (name "5VOR0V") (class "Default")
      (node (ref "R61") (pin "1") (pinfunction "1_1") (pintype "passive"))
      (node (ref "R64") (pin "1") (pinfunction "1_1") (pintype "passive"))
      (node (ref "R67") (pin "1") (pinfunction "1_1") (pintype "passive"))
      (node (ref "R70") (pin "1") (pinfunction "1_1") (pintype "passive"))
      (node (ref "SW1") (pin "2") (pinfunction "2_2") (pintype "passive"))
    )
    (net (code "24") (name "6") (class "Default")
      (node (ref "B1") (pin "6") (pinfunction "6_6") (pintype "bidirectional"))
      (node (ref "DASH") (pin "3") (pinfunction "K_RED_3") (pintype "bidirectional"))
    )
    (net (code "25") (name "7") (class "Default")
      (node (ref "B1") (pin "7") (pinfunction "7_7") (pintype "bidirectional"))
      (node (ref "DASH") (pin "4") (pinfunction "K_GREEN_4") (pintype "bidirectional"))
    )
    (net (code "26") (name "8") (class "Default")
      (node (ref "B1") (pin "8") (pinfunction "8_8") (pintype "bidirectional"))
      (node (ref "LAMBDAS") (pin "2") (pinfunction "K_BLUE_2") (pintype "bidirectional"))
    )
    (net (code "27") (name "9") (class "Default")
      (node (ref "B1") (pin "9") (pinfunction "9_9") (pintype "bidirectional"))
      (node (ref "LAMBDAS") (pin "3") (pinfunction "K_RED_3") (pintype "bidirectional"))
    )
    (net (code "28") (name "10") (class "Default")
      (node (ref "B1") (pin "10") (pinfunction "10_10") (pintype "bidirectional"))
      (node (ref "LAMBDAS") (pin "4") (pinfunction "K_GREEN_4") (pintype "bidirectional"))
    )
    (net (code "29") (name "12V") (class "Default")
      (node (ref "B1") (pin "VIN") (pinfunction "VIN_VIN") (pintype "bidirectional"))
      (node (ref "C26") (pin "2") (pinfunction "2_2") (pintype "passive"))
      (node (ref "J1") (pin "26") (pinfunction "26_26") (pintype "passive"))
      (node (ref "J1") (pin "54") (pinfunction "54_54") (pintype "passive"))
      (node (ref "J2") (pin "1") (pinfunction "1_1") (pintype "passive"))
    )
    (net (code "30") (name "14") (class "Default")
      (node (ref "B1") (pin "14") (pinfunction "14(TX3)_14") (pintype "bidirectional"))
      (node (ref "BRAKETEMP") (pin "3") (pinfunction "K_RED_3") (pintype "bidirectional"))
    )
    (net (code "31") (name "15") (class "Default")
      (node (ref "B1") (pin "15") (pinfunction "15(RX3)_15") (pintype "bidirectional"))
      (node (ref "BRAKETEMP") (pin "2") (pinfunction "K_BLUE_2") (pintype "bidirectional"))
    )
    (net (code "32") (name "16") (class "Default")
      (node (ref "B1") (pin "16") (pinfunction "16(TX2)_16") (pintype "bidirectional"))
      (node (ref "SHOCKPOT") (pin "4") (pinfunction "K_GREEN_4") (pintype "bidirectional"))
    )
    (net (code "33") (name "17") (class "Default")
      (node (ref "B1") (pin "17") (pinfunction "17(RX2)_17") (pintype "bidirectional"))
      (node (ref "SHOCKPOT") (pin "3") (pinfunction "K_RED_3") (pintype "bidirectional"))
    )
    (net (code "34") (name "18") (class "Default")
      (node (ref "B1") (pin "18") (pinfunction "18(TX1)_18") (pintype "bidirectional"))
      (node (ref "SHOCKPOT") (pin "2") (pinfunction "K_BLUE_2") (pintype "bidirectional"))
    )
    (net (code "35") (name "19") (class "Default")
      (node (ref "B1") (pin "19") (pinfunction "19(RX1)_19") (pintype "bidirectional"))
      (node (ref "BRAKEPRES") (pin "4") (pinfunction "K_GREEN_4") (pintype "bidirectional"))
    )
    (net (code "36") (name "22") (class "Default")
      (node (ref "B1") (pin "22") (pinfunction "22_22") (pintype "bidirectional"))
      (node (ref "BRAKEPRES") (pin "3") (pinfunction "K_RED_3") (pintype "bidirectional"))
    )
    (net (code "37") (name "23") (class "Default")
      (node (ref "B1") (pin "23") (pinfunction "23_23") (pintype "bidirectional"))
      (node (ref "BRAKEPRES") (pin "2") (pinfunction "K_BLUE_2") (pintype "bidirectional"))
    )
    (net (code "38") (name "24") (class "Default")
      (node (ref "B1") (pin "24") (pinfunction "24_24") (pintype "bidirectional"))
      (node (ref "INTAKEPRES") (pin "4") (pinfunction "K_GREEN_4") (pintype "bidirectional"))
    )
    (net (code "39") (name "25") (class "Default")
      (node (ref "B1") (pin "25") (pinfunction "25_25") (pintype "bidirectional"))
      (node (ref "INTAKEPRES") (pin "3") (pinfunction "K_RED_3") (pintype "bidirectional"))
    )
    (net (code "40") (name "26") (class "Default")
      (node (ref "B1") (pin "26") (pinfunction "26_26") (pintype "bidirectional"))
      (node (ref "INTAKEPRES") (pin "2") (pinfunction "K_BLUE_2") (pintype "bidirectional"))
    )
    (net (code "41") (name "27") (class "Default")
      (node (ref "B1") (pin "27") (pinfunction "27_27") (pintype "bidirectional"))
      (node (ref "INTAKETEMP") (pin "4") (pinfunction "K_GREEN_4") (pintype "bidirectional"))
    )
    (net (code "42") (name "28") (class "Default")
      (node (ref "B1") (pin "28") (pinfunction "28_28") (pintype "bidirectional"))
      (node (ref "INTAKETEMP") (pin "3") (pinfunction "K_RED_3") (pintype "bidirectional"))
    )
    (net (code "43") (name "29") (class "Default")
      (node (ref "B1") (pin "29") (pinfunction "29_29") (pintype "bidirectional"))
      (node (ref "INTAKETEMP") (pin "2") (pinfunction "K_BLUE_2") (pintype "bidirectional"))
    )
    (net (code "44") (name "30") (class "Default")
      (node (ref "B1") (pin "30") (pinfunction "30_30") (pintype "bidirectional"))
      (node (ref "COOLANTTEMP") (pin "4") (pinfunction "K_GREEN_4") (pintype "bidirectional"))
    )
    (net (code "45") (name "31") (class "Default")
      (node (ref "B1") (pin "31") (pinfunction "31_31") (pintype "bidirectional"))
      (node (ref "COOLANTTEMP") (pin "3") (pinfunction "K_RED_3") (pintype "bidirectional"))
    )
    (net (code "46") (name "32") (class "Default")
      (node (ref "B1") (pin "32") (pinfunction "32_32") (pintype "bidirectional"))
      (node (ref "COOLANTTEMP") (pin "2") (pinfunction "K_BLUE_2") (pintype "bidirectional"))
    )
    (net (code "47") (name "33") (class "Default")
      (node (ref "B1") (pin "33") (pinfunction "33_33") (pintype "bidirectional"))
      (node (ref "OILPRES") (pin "4") (pinfunction "K_GREEN_4") (pintype "bidirectional"))
    )
    (net (code "48") (name "34") (class "Default")
      (node (ref "B1") (pin "34") (pinfunction "34_34") (pintype "bidirectional"))
      (node (ref "OILPRES") (pin "3") (pinfunction "K_RED_3") (pintype "bidirectional"))
    )
    (net (code "49") (name "35") (class "Default")
      (node (ref "B1") (pin "35") (pinfunction "35_35") (pintype "bidirectional"))
      (node (ref "OILPRES") (pin "2") (pinfunction "K_BLUE_2") (pintype "bidirectional"))
    )
    (net (code "50") (name "36") (class "Default")
      (node (ref "B1") (pin "36") (pinfunction "36_36") (pintype "bidirectional"))
      (node (ref "OILTEMP") (pin "4") (pinfunction "K_GREEN_4") (pintype "bidirectional"))
    )
    (net (code "51") (name "37") (class "Default")
      (node (ref "B1") (pin "37") (pinfunction "37_37") (pintype "bidirectional"))
      (node (ref "OILTEMP") (pin "3") (pinfunction "K_RED_3") (pintype "bidirectional"))
    )
    (net (code "52") (name "38") (class "Default")
      (node (ref "B1") (pin "38") (pinfunction "38_38") (pintype "bidirectional"))
      (node (ref "OILTEMP") (pin "2") (pinfunction "K_BLUE_2") (pintype "bidirectional"))
    )
    (net (code "53") (name "39") (class "Default")
      (node (ref "B1") (pin "39") (pinfunction "39_39") (pintype "bidirectional"))
      (node (ref "SPARE1") (pin "4") (pinfunction "K_GREEN_4") (pintype "bidirectional"))
    )
    (net (code "54") (name "40") (class "Default")
      (node (ref "B1") (pin "40") (pinfunction "40_40") (pintype "bidirectional"))
      (node (ref "SPARE1") (pin "3") (pinfunction "K_RED_3") (pintype "bidirectional"))
    )
    (net (code "55") (name "41") (class "Default")
      (node (ref "B1") (pin "41") (pinfunction "41_41") (pintype "bidirectional"))
      (node (ref "SPARE1") (pin "2") (pinfunction "K_BLUE_2") (pintype "bidirectional"))
    )
    (net (code "56") (name "42") (class "Default")
      (node (ref "B1") (pin "42") (pinfunction "42_42") (pintype "bidirectional"))
      (node (ref "SPARE2") (pin "4") (pinfunction "K_GREEN_4") (pintype "bidirectional"))
    )
    (net (code "57") (name "43") (class "Default")
      (node (ref "B1") (pin "43") (pinfunction "43_43") (pintype "bidirectional"))
      (node (ref "SPARE2") (pin "3") (pinfunction "K_RED_3") (pintype "bidirectional"))
    )
    (net (code "58") (name "44") (class "Default")
      (node (ref "B1") (pin "44") (pinfunction "44_44") (pintype "bidirectional"))
      (node (ref "SPARE2") (pin "2") (pinfunction "K_BLUE_2") (pintype "bidirectional"))
    )
    (net (code "59") (name "45") (class "Default")
      (node (ref "B1") (pin "45") (pinfunction "45_45") (pintype "bidirectional"))
      (node (ref "DAQ") (pin "4") (pinfunction "K_GREEN_4") (pintype "bidirectional"))
    )
    (net (code "60") (name "46") (class "Default")
      (node (ref "B1") (pin "46") (pinfunction "46_46") (pintype "bidirectional"))
      (node (ref "DAQ") (pin "3") (pinfunction "K_RED_3") (pintype "bidirectional"))
    )
    (net (code "61") (name "47") (class "Default")
      (node (ref "B1") (pin "47") (pinfunction "47_47") (pintype "bidirectional"))
      (node (ref "DAQ") (pin "2") (pinfunction "K_BLUE_2") (pintype "bidirectional"))
    )
    (net (code "62") (name "48") (class "Default")
      (node (ref "B1") (pin "48") (pinfunction "48_48") (pintype "bidirectional"))
      (node (ref "R71") (pin "1") (pinfunction "1_1") (pintype "passive"))
      (node (ref "SW2") (pin "2") (pinfunction "2_2") (pintype "passive"))
    )
    (net (code "63") (name "A0") (class "Default")
      (node (ref "B1") (pin "A0") (pinfunction "A0(RX0)_A0") (pintype "bidirectional"))
      (node (ref "C6") (pin "2") (pinfunction "2_2") (pintype "passive"))
      (node (ref "R25") (pin "2") (pinfunction "2_2") (pintype "passive"))
    )
    (net (code "64") (name "A0IN") (class "Default")
      (node (ref "J1") (pin "18") (pinfunction "18_18") (pintype "passive"))
      (node (ref "R25") (pin "1") (pinfunction "1_1") (pintype "passive"))
    )
    (net (code "65") (name "A1") (class "Default")
      (node (ref "B1") (pin "A1") (pinfunction "A1(TX0)_A1") (pintype "bidirectional"))
      (node (ref "C7") (pin "2") (pinfunction "2_2") (pintype "passive"))
      (node (ref "R26") (pin "2") (pinfunction "2_2") (pintype "passive"))
    )
    (net (code "66") (name "A1IN") (class "Default")
      (node (ref "J1") (pin "19") (pinfunction "19_19") (pintype "passive"))
      (node (ref "R26") (pin "1") (pinfunction "1_1") (pintype "passive"))
    )
    (net (code "67") (name "A2") (class "Default")
      (node (ref "B1") (pin "A2") (pinfunction "A2_A2") (pintype "bidirectional"))
      (node (ref "C8") (pin "2") (pinfunction "2_2") (pintype "passive"))
      (node (ref "R27") (pin "2") (pinfunction "2_2") (pintype "passive"))
    )
    (net (code "68") (name "A2IN") (class "Default")
      (node (ref "J1") (pin "20") (pinfunction "20_20") (pintype "passive"))
      (node (ref "R27") (pin "1") (pinfunction "1_1") (pintype "passive"))
    )
    (net (code "69") (name "A3") (class "Default")
      (node (ref "B1") (pin "A3") (pinfunction "A3_A3") (pintype "bidirectional"))
      (node (ref "C9") (pin "2") (pinfunction "2_2") (pintype "passive"))
      (node (ref "R28") (pin "2") (pinfunction "2_2") (pintype "passive"))
    )
    (net (code "70") (name "A3IN") (class "Default")
      (node (ref "J1") (pin "10") (pinfunction "10_10") (pintype "passive"))
      (node (ref "R28") (pin "1") (pinfunction "1_1") (pintype "passive"))
    )
    (net (code "71") (name "A4") (class "Default")
      (node (ref "B1") (pin "A4") (pinfunction "A4_A4") (pintype "bidirectional"))
      (node (ref "C10") (pin "2") (pinfunction "2_2") (pintype "passive"))
      (node (ref "R29") (pin "2") (pinfunction "2_2") (pintype "passive"))
    )
    (net (code "72") (name "A4IN") (class "Default")
      (node (ref "J1") (pin "1") (pinfunction "1_1") (pintype "passive"))
      (node (ref "R29") (pin "1") (pinfunction "1_1") (pintype "passive"))
    )
    (net (code "73") (name "A5") (class "Default")
      (node (ref "B1") (pin "A5") (pinfunction "A5_A5") (pintype "bidirectional"))
      (node (ref "C11") (pin "2") (pinfunction "2_2") (pintype "passive"))
      (node (ref "R30") (pin "2") (pinfunction "2_2") (pintype "passive"))
    )
    (net (code "74") (name "A5IN") (class "Default")
      (node (ref "J1") (pin "11") (pinfunction "11_11") (pintype "passive"))
      (node (ref "R30") (pin "1") (pinfunction "1_1") (pintype "passive"))
    )
    (net (code "75") (name "A6") (class "Default")
      (node (ref "B1") (pin "A6") (pinfunction "A6_A6") (pintype "bidirectional"))
      (node (ref "C12") (pin "2") (pinfunction "2_2") (pintype "passive"))
      (node (ref "R31") (pin "2") (pinfunction "2_2") (pintype "passive"))
    )
    (net (code "76") (name "A6IN") (class "Default")
      (node (ref "J1") (pin "9") (pinfunction "9_9") (pintype "passive"))
      (node (ref "R31") (pin "1") (pinfunction "1_1") (pintype "passive"))
    )
    (net (code "77") (name "A7") (class "Default")
      (node (ref "B1") (pin "A7") (pinfunction "A7_A7") (pintype "bidirectional"))
      (node (ref "C13") (pin "2") (pinfunction "2_2") (pintype "passive"))
      (node (ref "R32") (pin "2") (pinfunction "2_2") (pintype "passive"))
    )
    (net (code "78") (name "A7IN") (class "Default")
      (node (ref "J1") (pin "17") (pinfunction "17_17") (pintype "passive"))
      (node (ref "R32") (pin "1") (pinfunction "1_1") (pintype "passive"))
    )
    (net (code "79") (name "A8") (class "Default")
      (node (ref "B1") (pin "A8") (pinfunction "A8_A8") (pintype "bidirectional"))
      (node (ref "C14") (pin "2") (pinfunction "2_2") (pintype "passive"))
      (node (ref "R33") (pin "2") (pinfunction "2_2") (pintype "passive"))
    )
    (net (code "80") (name "A8IN") (class "Default")
      (node (ref "J1") (pin "8") (pinfunction "8_8") (pintype "passive"))
      (node (ref "R33") (pin "1") (pinfunction "1_1") (pintype "passive"))
    )
    (net (code "81") (name "A9") (class "Default")
      (node (ref "B1") (pin "A9") (pinfunction "A9_A9") (pintype "bidirectional"))
      (node (ref "C15") (pin "2") (pinfunction "2_2") (pintype "passive"))
      (node (ref "R34") (pin "2") (pinfunction "2_2") (pintype "passive"))
    )
    (net (code "82") (name "A9IN") (class "Default")
      (node (ref "J1") (pin "16") (pinfunction "16_16") (pintype "passive"))
      (node (ref "R34") (pin "1") (pinfunction "1_1") (pintype "passive"))
    )
    (net (code "83") (name "A10") (class "Default")
      (node (ref "B1") (pin "A10") (pinfunction "A10_A10") (pintype "bidirectional"))
      (node (ref "C16") (pin "2") (pinfunction "2_2") (pintype "passive"))
      (node (ref "R35") (pin "2") (pinfunction "2_2") (pintype "passive"))
    )
    (net (code "84") (name "A10IN") (class "Default")
      (node (ref "J1") (pin "7") (pinfunction "7_7") (pintype "passive"))
      (node (ref "R35") (pin "1") (pinfunction "1_1") (pintype "passive"))
    )
    (net (code "85") (name "A11") (class "Default")
      (node (ref "B1") (pin "A11") (pinfunction "A11_A11") (pintype "bidirectional"))
      (node (ref "C17") (pin "2") (pinfunction "2_2") (pintype "passive"))
      (node (ref "R36") (pin "2") (pinfunction "2_2") (pintype "passive"))
    )
    (net (code "86") (name "A11IN") (class "Default")
      (node (ref "J1") (pin "6") (pinfunction "6_6") (pintype "passive"))
      (node (ref "R36") (pin "1") (pinfunction "1_1") (pintype "passive"))
    )
    (net (code "87") (name "A12") (class "Default")
      (node (ref "B1") (pin "A12") (pinfunction "A12_A12") (pintype "bidirectional"))
      (node (ref "C18") (pin "2") (pinfunction "2_2") (pintype "passive"))
      (node (ref "R37") (pin "2") (pinfunction "2_2") (pintype "passive"))
    )
    (net (code "88") (name "A12IN") (class "Default")
      (node (ref "J1") (pin "13") (pinfunction "13_13") (pintype "passive"))
      (node (ref "R37") (pin "1") (pinfunction "1_1") (pintype "passive"))
    )
    (net (code "89") (name "A13") (class "Default")
      (node (ref "B1") (pin "A13") (pinfunction "A13_A13") (pintype "bidirectional"))
      (node (ref "C19") (pin "2") (pinfunction "2_2") (pintype "passive"))
      (node (ref "R38") (pin "2") (pinfunction "2_2") (pintype "passive"))
    )
    (net (code "90") (name "A13IN") (class "Default")
      (node (ref "J1") (pin "4") (pinfunction "4_4") (pintype "passive"))
      (node (ref "R38") (pin "1") (pinfunction "1_1") (pintype "passive"))
    )
    (net (code "91") (name "A14") (class "Default")
      (node (ref "B1") (pin "A14") (pinfunction "A14_A14") (pintype "bidirectional"))
      (node (ref "C20") (pin "2") (pinfunction "2_2") (pintype "passive"))
      (node (ref "R39") (pin "2") (pinfunction "2_2") (pintype "passive"))
    )
    (net (code "92") (name "A14IN") (class "Default")
      (node (ref "J1") (pin "5") (pinfunction "5_5") (pintype "passive"))
      (node (ref "R39") (pin "1") (pinfunction "1_1") (pintype "passive"))
    )
    (net (code "93") (name "A15") (class "Default")
      (node (ref "B1") (pin "A15") (pinfunction "A15_A15") (pintype "bidirectional"))
      (node (ref "C21") (pin "2") (pinfunction "2_2") (pintype "passive"))
      (node (ref "R40") (pin "2") (pinfunction "2_2") (pintype "passive"))
    )
    (net (code "94") (name "A15IN") (class "Default")
      (node (ref "J1") (pin "14") (pinfunction "14_14") (pintype "passive"))
      (node (ref "R40") (pin "1") (pinfunction "1_1") (pintype "passive"))
    )
    (net (code "95") (name "AREF") (class "Default")
      (node (ref "U4") (pin "AREF") (pinfunction "AREF_AREF") (pintype "bidirectional"))
    )
    (net (code "96") (name "CALIB") (class "Default")
      (node (ref "B1") (pin "13") (pinfunction "13_13") (pintype "bidirectional"))
      (node (ref "J1") (pin "31") (pinfunction "31_31") (pintype "passive"))
      (node (ref "R50") (pin "1") (pinfunction "1_1") (pintype "passive"))
    )
    (net (code "97") (name "CANHI") (class "Default")
      (node (ref "J1") (pin "60") (pinfunction "60_60") (pintype "passive"))
      (node (ref "JP1") (pin "3") (pinfunction "3_3") (pintype "passive"))
    )
    (net (code "98") (name "CANLO") (class "Default")
      (node (ref "J1") (pin "53") (pinfunction "53_53") (pintype "passive"))
      (node (ref "JP1") (pin "4") (pinfunction "4_4") (pintype "passive"))
    )
    (net (code "99") (name "CAN_CS") (class "Default")
      (node (ref "B1") (pin "49") (pinfunction "49_49") (pintype "bidirectional"))
      (node (ref "U4") (pin "D10") (pinfunction "*D10_D10") (pintype "bidirectional"))
    )
    (net (code "100") (name "CAN_INT") (class "Default")
      (node (ref "U4") (pin "D2") (pinfunction "D2_D2") (pintype "bidirectional"))
    )
    (net (code "101") (name "D3") (class "Default")
      (node (ref "U4") (pin "D3") (pinfunction "*D3_D3") (pintype "bidirectional"))
    )
    (net (code "102") (name "D4") (class "Default")
      (node (ref "U4") (pin "D4") (pinfunction "D4_D4") (pintype "bidirectional"))
    )
    (net (code "103") (name "D5") (class "Default")
      (node (ref "U4") (pin "D5") (pinfunction "*D5_D5") (pintype "bidirectional"))
    )
    (net (code "104") (name "DIN") (class "Default")
      (node (ref "Q1") (pin "2") (pinfunction "S_2") (pintype "passive"))
      (node (ref "R3") (pin "1") (pinfunction "1_1") (pintype "passive"))
      (node (ref "XB1") (pin "3") (pinfunction "DIN/~{CONFIG}_3") (pintype "input"))
    )
    (net (code "105") (name "DOUT") (class "Default")
      (node (ref "Q2") (pin "2") (pinfunction "S_2") (pintype "passive"))
      (node (ref "R1") (pin "1") (pinfunction "1_1") (pintype "passive"))
      (node (ref "XB1") (pin "2") (pinfunction "DOUT_2") (pintype "output"))
    )
    (net (code "106") (name "FL_WS") (class "Default")
      (node (ref "B1") (pin "2") (pinfunction "2_2") (pintype "bidirectional"))
      (node (ref "J1") (pin "25") (pinfunction "25_25") (pintype "passive"))
      (node (ref "R47") (pin "2") (pinfunction "2_2") (pintype "passive"))
    )
    (net (code "107") (name "FR_WS") (class "Default")
      (node (ref "B1") (pin "3") (pinfunction "3_3") (pintype "bidirectional"))
      (node (ref "J1") (pin "34") (pinfunction "34_34") (pintype "passive"))
      (node (ref "R48") (pin "2") (pinfunction "2_2") (pintype "passive"))
    )
    (net (code "108") (name "GND") (class "Default")
      (node (ref "B1") (pin "GND@0") (pinfunction "GND_GND@0") (pintype "bidirectional"))
      (node (ref "C1") (pin "1") (pinfunction "1_1") (pintype "passive"))
      (node (ref "C10") (pin "1") (pinfunction "1_1") (pintype "passive"))
      (node (ref "C11") (pin "1") (pinfunction "1_1") (pintype "passive"))
      (node (ref "C12") (pin "1") (pinfunction "1_1") (pintype "passive"))
      (node (ref "C13") (pin "1") (pinfunction "1_1") (pintype "passive"))
      (node (ref "C14") (pin "1") (pinfunction "1_1") (pintype "passive"))
      (node (ref "C15") (pin "1") (pinfunction "1_1") (pintype "passive"))
      (node (ref "C16") (pin "1") (pinfunction "1_1") (pintype "passive"))
      (node (ref "C17") (pin "1") (pinfunction "1_1") (pintype "passive"))
      (node (ref "C18") (pin "1") (pinfunction "1_1") (pintype "passive"))
      (node (ref "C19") (pin "1") (pinfunction "1_1") (pintype "passive"))
      (node (ref "C2") (pin "2") (pinfunction "2_2") (pintype "passive"))
      (node (ref "C20") (pin "1") (pinfunction "1_1") (pintype "passive"))
      (node (ref "C21") (pin "1") (pinfunction "1_1") (pintype "passive"))
      (node (ref "C22") (pin "1") (pinfunction "1_1") (pintype "passive"))
      (node (ref "C23") (pin "2") (pinfunction "2_2") (pintype "passive"))
      (node (ref "C24") (pin "1") (pinfunction "1_1") (pintype "passive"))
      (node (ref "C25") (pin "2") (pinfunction "2_2") (pintype "passive"))
      (node (ref "C26") (pin "1") (pinfunction "1_1") (pintype "passive"))
      (node (ref "C27") (pin "1") (pinfunction "1_1") (pintype "passive"))
      (node (ref "C28") (pin "1") (pinfunction "1_1") (pintype "passive"))
      (node (ref "C29") (pin "1") (pinfunction "1_1") (pintype "passive"))
      (node (ref "C3") (pin "1") (pinfunction "1_1") (pintype "passive"))
      (node (ref "C30") (pin "1") (pinfunction "1_1") (pintype "passive"))
      (node (ref "C31") (pin "1") (pinfunction "1_1") (pintype "passive"))
      (node (ref "C32") (pin "1") (pinfunction "1_1") (pintype "passive"))
      (node (ref "C33") (pin "1") (pinfunction "1_1") (pintype "passive"))
      (node (ref "C34") (pin "1") (pinfunction "1_1") (pintype "passive"))
      (node (ref "C35") (pin "1") (pinfunction "1_1") (pintype "passive"))
      (node (ref "C4") (pin "1") (pinfunction "1_1") (pintype "passive"))
      (node (ref "C5") (pin "1") (pinfunction "1_1") (pintype "passive"))
      (node (ref "C6") (pin "1") (pinfunction "1_1") (pintype "passive"))
      (node (ref "C7") (pin "1") (pinfunction "1_1") (pintype "passive"))
      (node (ref "C8") (pin "1") (pinfunction "1_1") (pintype "passive"))
      (node (ref "C9") (pin "1") (pinfunction "1_1") (pintype "passive"))
      (node (ref "IC1") (pin "4") (pinfunction "GND_4") (pintype "bidirectional"))
      (node (ref "J1") (pin "21") (pinfunction "21_21") (pintype "passive"))
      (node (ref "J1") (pin "22") (pinfunction "22_22") (pintype "passive"))
      (node (ref "J1") (pin "23") (pinfunction "23_23") (pintype "passive"))
      (node (ref "J1") (pin "24") (pinfunction "24_24") (pintype "passive"))
      (node (ref "J1") (pin "50") (pinfunction "50_50") (pintype "passive"))
      (node (ref "J1") (pin "51") (pinfunction "51_51") (pintype "passive"))
      (node (ref "J1") (pin "52") (pinfunction "52_52") (pintype "passive"))
      (node (ref "J2") (pin "2") (pinfunction "2_2") (pintype "passive"))
      (node (ref "JP1") (pin "2") (pinfunction "2_2") (pintype "passive"))
      (node (ref "R59") (pin "2") (pinfunction "2_2") (pintype "passive"))
      (node (ref "R6") (pin "1") (pinfunction "1_1") (pintype "passive"))
      (node (ref "R62") (pin "2") (pinfunction "2_2") (pintype "passive"))
      (node (ref "R65") (pin "2") (pinfunction "2_2") (pintype "passive"))
      (node (ref "R68") (pin "2") (pinfunction "2_2") (pintype "passive"))
      (node (ref "R71") (pin "2") (pinfunction "2_2") (pintype "passive"))
      (node (ref "U1") (pin "2") (pinfunction "VSS_2") (pintype "passive"))
      (node (ref "U4") (pin "GND@0") (pinfunction "GND_GND@0") (pintype "bidirectional"))
      (node (ref "U4") (pin "GND@1") (pinfunction "GND_GND@1") (pintype "bidirectional"))
      (node (ref "U4") (pin "GND@2") (pinfunction "GND_GND@2") (pintype "bidirectional"))
      (node (ref "U6") (pin "4") (pinfunction "DGND_4") (pintype "power_in"))
      (node (ref "U6") (pin "5") (pinfunction "AGND_5") (pintype "power_in"))
      (node (ref "U7") (pin "4") (pinfunction "DGND_4") (pintype "power_in"))
      (node (ref "U7") (pin "5") (pinfunction "AGND_5") (pintype "power_in"))
      (node (ref "XB1") (pin "10") (pinfunction "GND_10") (pintype "power_in"))
    )
    (net (code "109") (name "JOY-CLICK") (class "Default")
      (node (ref "U4") (pin "A4") (pinfunction "A4_A4") (pintype "bidirectional"))
    )
    (net (code "110") (name "JOY-DOWN") (class "Default")
      (node (ref "U4") (pin "A3") (pinfunction "A3_A3") (pintype "bidirectional"))
    )
    (net (code "111") (name "JOY-LEFT") (class "Default")
      (node (ref "U4") (pin "A2") (pinfunction "A2_A2") (pintype "bidirectional"))
    )
    (net (code "112") (name "JOY-RIGHT") (class "Default")
      (node (ref "U4") (pin "A5") (pinfunction "A5_A5") (pintype "bidirectional"))
    )
    (net (code "113") (name "JOY-UP") (class "Default")
      (node (ref "U4") (pin "A1") (pinfunction "A1_A1") (pintype "bidirectional"))
    )
    (net (code "114") (name "LCD") (class "Default")
      (node (ref "U4") (pin "D6") (pinfunction "*D6_D6") (pintype "bidirectional"))
    )
    (net (code "115") (name "LCL") (class "Default")
      (node (ref "IC1") (pin "7") (pinfunction "LY_7") (pintype "bidirectional"))
      (node (ref "J1") (pin "35") (pinfunction "35_35") (pintype "passive"))
      (node (ref "J1") (pin "36") (pinfunction "36_36") (pintype "passive"))
      (node (ref "J1") (pin "37") (pinfunction "37_37") (pintype "passive"))
      (node (ref "J1") (pin "38") (pinfunction "38_38") (pintype "passive"))
      (node (ref "J1") (pin "39") (pinfunction "39_39") (pintype "passive"))
      (node (ref "J1") (pin "40") (pinfunction "40_40") (pintype "passive"))
      (node (ref "J1") (pin "41") (pinfunction "41_41") (pintype "passive"))
      (node (ref "J1") (pin "42") (pinfunction "42_42") (pintype "passive"))
      (node (ref "J1") (pin "43") (pinfunction "43_43") (pintype "passive"))
      (node (ref "J1") (pin "44") (pinfunction "44_44") (pintype "passive"))
      (node (ref "J1") (pin "45") (pinfunction "45_45") (pintype "passive"))
      (node (ref "J1") (pin "46") (pinfunction "46_46") (pintype "passive"))
      (node (ref "J1") (pin "47") (pinfunction "47_47") (pintype "passive"))
      (node (ref "J1") (pin "48") (pinfunction "48_48") (pintype "passive"))
      (node (ref "J1") (pin "49") (pinfunction "49_49") (pintype "passive"))
      (node (ref "J1") (pin "57") (pinfunction "57_57") (pintype "passive"))
      (node (ref "R10") (pin "1") (pinfunction "1_1") (pintype "passive"))
    )
    (net (code "116") (name "LDA") (class "Default")
      (node (ref "IC1") (pin "2") (pinfunction "LX_2") (pintype "bidirectional"))
      (node (ref "J1") (pin "32") (pinfunction "32_32") (pintype "passive"))
      (node (ref "R9") (pin "2") (pinfunction "2_2") (pintype "passive"))
    )
    (net (code "117") (name "LED1") (class "Default")
      (node (ref "U4") (pin "D8") (pinfunction "D8_D8") (pintype "bidirectional"))
    )
    (net (code "118") (name "LED2") (class "Default")
      (node (ref "U4") (pin "D7") (pinfunction "D7_D7") (pintype "bidirectional"))
    )
    (net (code "119") (name "MISO") (class "Default")
      (node (ref "B1") (pin "50") (pinfunction "50_50") (pintype "bidirectional"))
      (node (ref "U4") (pin "D12") (pinfunction "D12_D12") (pintype "bidirectional"))
    )
    (net (code "120") (name "MOSI") (class "Default")
      (node (ref "B1") (pin "51") (pinfunction "51_51") (pintype "bidirectional"))
      (node (ref "U4") (pin "D11") (pinfunction "*D11_D11") (pintype "bidirectional"))
    )
    (net (code "121") (name "Net-(BRAKEPRES-COMMON_ANODE)") (class "Default")
      (node (ref "BRAKEPRES") (pin "1") (pinfunction "COMMON_ANODE_1") (pintype "bidirectional"))
      (node (ref "R15") (pin "1") (pinfunction "1_1") (pintype "passive"))
    )
    (net (code "122") (name "Net-(BRAKETEMP-COMMON_ANODE)") (class "Default")
      (node (ref "BRAKETEMP") (pin "1") (pinfunction "COMMON_ANODE_1") (pintype "bidirectional"))
      (node (ref "R13") (pin "1") (pinfunction "1_1") (pintype "passive"))
    )
    (net (code "123") (name "Net-(COOLANTTEMP-COMMON_ANODE)") (class "Default")
      (node (ref "COOLANTTEMP") (pin "1") (pinfunction "COMMON_ANODE_1") (pintype "bidirectional"))
      (node (ref "R18") (pin "1") (pinfunction "1_1") (pintype "passive"))
    )
    (net (code "124") (name "Net-(DAQ-COMMON_ANODE)") (class "Default")
      (node (ref "DAQ") (pin "1") (pinfunction "COMMON_ANODE_1") (pintype "bidirectional"))
      (node (ref "R23") (pin "1") (pinfunction "1_1") (pintype "passive"))
    )
    (net (code "125") (name "Net-(DASH-COMMON_ANODE)") (class "Default")
      (node (ref "DASH") (pin "1") (pinfunction "COMMON_ANODE_1") (pintype "bidirectional"))
      (node (ref "R11") (pin "1") (pinfunction "1_1") (pintype "passive"))
    )
    (net (code "126") (name "Net-(INTAKEPRES-COMMON_ANODE)") (class "Default")
      (node (ref "INTAKEPRES") (pin "1") (pinfunction "COMMON_ANODE_1") (pintype "bidirectional"))
      (node (ref "R16") (pin "1") (pinfunction "1_1") (pintype "passive"))
    )
    (net (code "127") (name "Net-(INTAKETEMP-COMMON_ANODE)") (class "Default")
      (node (ref "INTAKETEMP") (pin "1") (pinfunction "COMMON_ANODE_1") (pintype "bidirectional"))
      (node (ref "R17") (pin "1") (pinfunction "1_1") (pintype "passive"))
    )
    (net (code "128") (name "Net-(LAMBDAS-COMMON_ANODE)") (class "Default")
      (node (ref "LAMBDAS") (pin "1") (pinfunction "COMMON_ANODE_1") (pintype "bidirectional"))
      (node (ref "R12") (pin "1") (pinfunction "1_1") (pintype "passive"))
    )
    (net (code "129") (name "Net-(OILPRES-COMMON_ANODE)") (class "Default")
      (node (ref "OILPRES") (pin "1") (pinfunction "COMMON_ANODE_1") (pintype "bidirectional"))
      (node (ref "R19") (pin "1") (pinfunction "1_1") (pintype "passive"))
    )
    (net (code "130") (name "Net-(OILTEMP-COMMON_ANODE)") (class "Default")
      (node (ref "OILTEMP") (pin "1") (pinfunction "COMMON_ANODE_1") (pintype "bidirectional"))
      (node (ref "R20") (pin "1") (pinfunction "1_1") (pintype "passive"))
    )
    (net (code "131") (name "Net-(R24-Pad2)") (class "Default")
      (node (ref "R24") (pin "2") (pinfunction "2_2") (pintype "passive"))
      (node (ref "REC") (pin "2") (pinfunction "2_2") (pintype "passive"))
    )
    (net (code "132") (name "Net-(R51-Pad2)") (class "Default")
      (node (ref "R51") (pin "2") (pinfunction "2_2") (pintype "passive"))
      (node (ref "R59") (pin "1") (pinfunction "1_1") (pintype "passive"))
      (node (ref "R60") (pin "2") (pinfunction "2_2") (pintype "passive"))
    )
    (net (code "133") (name "Net-(R53-Pad2)") (class "Default")
      (node (ref "R53") (pin "2") (pinfunction "2_2") (pintype "passive"))
      (node (ref "R62") (pin "1") (pinfunction "1_1") (pintype "passive"))
      (node (ref "R63") (pin "2") (pinfunction "2_2") (pintype "passive"))
    )
    (net (code "134") (name "Net-(R55-Pad2)") (class "Default")
      (node (ref "R55") (pin "2") (pinfunction "2_2") (pintype "passive"))
      (node (ref "R65") (pin "1") (pinfunction "1_1") (pintype "passive"))
      (node (ref "R66") (pin "2") (pinfunction "2_2") (pintype "passive"))
    )
    (net (code "135") (name "Net-(R57-Pad2)") (class "Default")
      (node (ref "R57") (pin "2") (pinfunction "2_2") (pintype "passive"))
      (node (ref "R68") (pin "1") (pinfunction "1_1") (pintype "passive"))
      (node (ref "R69") (pin "2") (pinfunction "2_2") (pintype "passive"))
    )
    (net (code "136") (name "Net-(SHOCKPOT-COMMON_ANODE)") (class "Default")
      (node (ref "R14") (pin "1") (pinfunction "1_1") (pintype "passive"))
      (node (ref "SHOCKPOT") (pin "1") (pinfunction "COMMON_ANODE_1") (pintype "bidirectional"))
    )
    (net (code "137") (name "Net-(SPARE1-COMMON_ANODE)") (class "Default")
      (node (ref "R21") (pin "1") (pinfunction "1_1") (pintype "passive"))
      (node (ref "SPARE1") (pin "1") (pinfunction "COMMON_ANODE_1") (pintype "bidirectional"))
    )
    (net (code "138") (name "Net-(SPARE2-COMMON_ANODE)") (class "Default")
      (node (ref "R22") (pin "1") (pinfunction "1_1") (pintype "passive"))
      (node (ref "SPARE2") (pin "1") (pinfunction "COMMON_ANODE_1") (pintype "bidirectional"))
    )
    (net (code "139") (name "Net-(U1-CE)") (class "Default")
      (node (ref "R5") (pin "2") (pinfunction "2_2") (pintype "passive"))
      (node (ref "R6") (pin "2") (pinfunction "2_2") (pintype "passive"))
      (node (ref "U1") (pin "3") (pinfunction "CE_3") (pintype "passive"))
    )
    (net (code "140") (name "Net-(U6-DRDY_N)") (class "Default")
      (node (ref "R43") (pin "1") (pinfunction "1_1") (pintype "passive"))
      (node (ref "U6") (pin "14") (pinfunction "DRDY_N_14") (pintype "output"))
    )
    (net (code "141") (name "Net-(U6-REFN)") (class "Default")
      (node (ref "R42") (pin "2") (pinfunction "2_2") (pintype "passive"))
      (node (ref "U6") (pin "8") (pinfunction "REFN_8") (pintype "input"))
    )
    (net (code "142") (name "Net-(U6-REFP)") (class "Default")
      (node (ref "R41") (pin "2") (pinfunction "2_2") (pintype "passive"))
      (node (ref "U6") (pin "9") (pinfunction "REFP_9") (pintype "input"))
    )
    (net (code "143") (name "Net-(U7-DRDY_N)") (class "Default")
      (node (ref "R46") (pin "1") (pinfunction "1_1") (pintype "passive"))
      (node (ref "U7") (pin "14") (pinfunction "DRDY_N_14") (pintype "output"))
    )
    (net (code "144") (name "Net-(U7-REFN)") (class "Default")
      (node (ref "R45") (pin "2") (pinfunction "2_2") (pintype "passive"))
      (node (ref "U7") (pin "8") (pinfunction "REFN_8") (pintype "input"))
    )
    (net (code "145") (name "Net-(U7-REFP)") (class "Default")
      (node (ref "R44") (pin "2") (pinfunction "2_2") (pintype "passive"))
      (node (ref "U7") (pin "9") (pinfunction "REFP_9") (pintype "input"))
    )
    (net (code "146") (name "Net-(XB1-~{DTR}{slash}SLEEP_RQ{slash}DI8)") (class "Default")
      (node (ref "R8") (pin "2") (pinfunction "2_2") (pintype "passive"))
      (node (ref "XB1") (pin "9") (pinfunction "~{DTR}/SLEEP_RQ/DI8_9") (pintype "bidirectional"))
    )
    (net (code "147") (name "Net-(XB1-~{RTS}{slash}AD6{slash}DIO6)") (class "Default")
      (node (ref "R7") (pin "2") (pinfunction "2_2") (pintype "passive"))
      (node (ref "XB1") (pin "16") (pinfunction "~{RTS}/AD6/DIO6_16") (pintype "bidirectional"))
    )
    (net (code "148") (name "REC") (class "Default")
      (node (ref "B1") (pin "11") (pinfunction "11_11") (pintype "bidirectional"))
      (node (ref "J1") (pin "33") (pinfunction "33_33") (pintype "passive"))
      (node (ref "R49") (pin "2") (pinfunction "2_2") (pintype "passive"))
      (node (ref "REC") (pin "1") (pinfunction "1_1") (pintype "passive"))
    )
    (net (code "149") (name "RS") (class "Default")
      (node (ref "U4") (pin "RES") (pinfunction "RES_RES") (pintype "bidirectional"))
    )
    (net (code "150") (name "RX") (class "Default")
      (node (ref "U4") (pin "RX") (pinfunction "RX_RX") (pintype "bidirectional"))
    )
    (net (code "151") (name "RX0") (class "Default")
      (node (ref "B1") (pin "0") (pinfunction "0(RX0)_0") (pintype "bidirectional"))
      (node (ref "Q2") (pin "3") (pinfunction "D_3") (pintype "passive"))
      (node (ref "R2") (pin "1") (pinfunction "1_1") (pintype "passive"))
    )
    (net (code "152") (name "SCK") (class "Default")
      (node (ref "B1") (pin "52") (pinfunction "52_52") (pintype "bidirectional"))
      (node (ref "U4") (pin "D13") (pinfunction "D13_D13") (pintype "bidirectional"))
    )
    (net (code "153") (name "SCL") (class "Default")
      (node (ref "B1") (pin "21") (pinfunction "21(SCL)_21") (pintype "bidirectional"))
      (node (ref "IC1") (pin "6") (pinfunction "SY_6") (pintype "bidirectional"))
      (node (ref "U6") (pin "16") (pinfunction "SCL_16") (pintype "input"))
      (node (ref "U6") (pin "2") (pinfunction "A1_2") (pintype "input"))
      (node (ref "U7") (pin "1") (pinfunction "A0_1") (pintype "input"))
      (node (ref "U7") (pin "16") (pinfunction "SCL_16") (pintype "input"))
    )
    (net (code "154") (name "SDA") (class "Default")
      (node (ref "B1") (pin "20") (pinfunction "20(SDA)_20") (pintype "bidirectional"))
      (node (ref "IC1") (pin "3") (pinfunction "SX_3") (pintype "bidirectional"))
      (node (ref "U6") (pin "1") (pinfunction "A0_1") (pintype "input"))
      (node (ref "U6") (pin "15") (pinfunction "SDA_15") (pintype "bidirectional"))
      (node (ref "U7") (pin "15") (pinfunction "SDA_15") (pintype "bidirectional"))
      (node (ref "U7") (pin "2") (pinfunction "A1_2") (pintype "input"))
    )
    (net (code "155") (name "SD_CS") (class "Default")
      (node (ref "B1") (pin "53") (pinfunction "53_53") (pintype "bidirectional"))
      (node (ref "U4") (pin "D9") (pinfunction "*D9_D9") (pintype "bidirectional"))
    )
    (net (code "156") (name "SG_11") (class "Default")
      (node (ref "J1") (pin "30") (pinfunction "30_30") (pintype "passive"))
      (node (ref "R58") (pin "2") (pinfunction "2_2") (pintype "passive"))
      (node (ref "R70") (pin "2") (pinfunction "2_2") (pintype "passive"))
    )
    (net (code "157") (name "SG_21") (class "Default")
      (node (ref "J1") (pin "29") (pinfunction "29_29") (pintype "passive"))
      (node (ref "R56") (pin "2") (pinfunction "2_2") (pintype "passive"))
      (node (ref "R67") (pin "2") (pinfunction "2_2") (pintype "passive"))
    )
    (net (code "158") (name "SG_31") (class "Default")
      (node (ref "J1") (pin "28") (pinfunction "28_28") (pintype "passive"))
      (node (ref "R54") (pin "2") (pinfunction "2_2") (pintype "passive"))
      (node (ref "R64") (pin "2") (pinfunction "2_2") (pintype "passive"))
    )
    (net (code "159") (name "SG_41") (class "Default")
      (node (ref "J1") (pin "27") (pinfunction "27_27") (pintype "passive"))
      (node (ref "R52") (pin "2") (pinfunction "2_2") (pintype "passive"))
      (node (ref "R61") (pin "2") (pinfunction "2_2") (pintype "passive"))
    )
    (net (code "160") (name "TX") (class "Default")
      (node (ref "U4") (pin "TX") (pinfunction "TX_TX") (pintype "bidirectional"))
    )
    (net (code "161") (name "TX0") (class "Default")
      (node (ref "B1") (pin "1") (pinfunction "1(TX0)_1") (pintype "bidirectional"))
      (node (ref "Q1") (pin "3") (pinfunction "D_3") (pintype "passive"))
      (node (ref "R4") (pin "1") (pinfunction "1_1") (pintype "passive"))
    )
    (net (code "162") (name "unconnected-(B1-5V-Pad5V@1)") (class "Default")
      (node (ref "B1") (pin "5V@1") (pinfunction "5V_5V@1") (pintype "bidirectional"))
    )
    (net (code "163") (name "unconnected-(B1-5V-Pad5V@2)") (class "Default")
      (node (ref "B1") (pin "5V@2") (pinfunction "5V_5V@2") (pintype "bidirectional"))
    )
    (net (code "164") (name "unconnected-(B1-GND-PadGND@1)") (class "Default")
      (node (ref "B1") (pin "GND@1") (pinfunction "GND_GND@1") (pintype "bidirectional"))
    )
    (net (code "165") (name "unconnected-(B1-GND-PadGND@2)") (class "Default")
      (node (ref "B1") (pin "GND@2") (pinfunction "GND_GND@2") (pintype "bidirectional"))
    )
    (net (code "166") (name "unconnected-(B1-GND-PadGND@3)") (class "Default")
      (node (ref "B1") (pin "GND@3") (pinfunction "GND_GND@3") (pintype "bidirectional"))
    )
    (net (code "167") (name "unconnected-(B1-GND-PadGND@4)") (class "Default")
      (node (ref "B1") (pin "GND@4") (pinfunction "GND_GND@4") (pintype "bidirectional"))
    )
    (net (code "168") (name "unconnected-(B1-Pad3.3V)") (class "Default")
      (node (ref "B1") (pin "3.3V") (pinfunction "3.3V_3.3V") (pintype "bidirectional"))
    )
    (net (code "169") (name "unconnected-(B1-Pad12)") (class "Default")
      (node (ref "B1") (pin "12") (pinfunction "12_12") (pintype "bidirectional"))
    )
    (net (code "170") (name "unconnected-(B1-PadAREF)") (class "Default")
      (node (ref "B1") (pin "AREF") (pinfunction "AREF_AREF") (pintype "bidirectional"))
    )
    (net (code "171") (name "unconnected-(B1-PadRESET)") (class "Default")
      (node (ref "B1") (pin "RESET") (pinfunction "RESET_RESET") (pintype "bidirectional"))
    )
    (net (code "172") (name "unconnected-(IC1-NC_1-Pad1)") (class "Default")
      (node (ref "IC1") (pin "1") (pinfunction "NC_1_1") (pintype "bidirectional"))
    )
    (net (code "173") (name "unconnected-(IC1-NC_2-Pad5)") (class "Default")
      (node (ref "IC1") (pin "5") (pinfunction "NC_2_5") (pintype "bidirectional"))
    )
    (net (code "174") (name "unconnected-(J1-Pad2)") (class "Default")
      (node (ref "J1") (pin "2") (pinfunction "2_2") (pintype "passive"))
    )
    (net (code "175") (name "unconnected-(J1-Pad3)") (class "Default")
      (node (ref "J1") (pin "3") (pinfunction "3_3") (pintype "passive"))
    )
    (net (code "176") (name "unconnected-(J1-Pad55)") (class "Default")
      (node (ref "J1") (pin "55") (pinfunction "55_55") (pintype "passive"))
    )
    (net (code "177") (name "unconnected-(J1-Pad56)") (class "Default")
      (node (ref "J1") (pin "56") (pinfunction "56_56") (pintype "passive"))
    )
    (net (code "178") (name "unconnected-(J1-Pad58)") (class "Default")
      (node (ref "J1") (pin "58") (pinfunction "58_58") (pintype "passive"))
    )
    (net (code "179") (name "unconnected-(J1-Pad59)") (class "Default")
      (node (ref "J1") (pin "59") (pinfunction "59_59") (pintype "passive"))
    )
    (net (code "180") (name "unconnected-(U1-NC-Pad4)") (class "Default")
      (node (ref "U1") (pin "4") (pinfunction "NC_4") (pintype "no_connect"))
    )
    (net (code "181") (name "unconnected-(U4-Pad3.3V)") (class "Default")
      (node (ref "U4") (pin "3.3V") (pinfunction "3.3V_3.3V") (pintype "bidirectional"))
    )
    (net (code "182") (name "unconnected-(U4-PadA0)") (class "Default")
      (node (ref "U4") (pin "A0") (pinfunction "A0_A0") (pintype "bidirectional"))
    )
    (net (code "183") (name "unconnected-(U4-PadIOREF)") (class "Default")
      (node (ref "U4") (pin "IOREF") (pinfunction "IOREF_IOREF") (pintype "bidirectional"))
    )
    (net (code "184") (name "unconnected-(U4-PadSCL)") (class "Default")
      (node (ref "U4") (pin "SCL") (pinfunction "SCL_SCL") (pintype "bidirectional"))
    )
    (net (code "185") (name "unconnected-(U4-PadSDA)") (class "Default")
      (node (ref "U4") (pin "SDA") (pinfunction "SDA_SDA") (pintype "bidirectional"))
    )
    (net (code "186") (name "unconnected-(U4-PadVIN)") (class "Default")
      (node (ref "U4") (pin "VIN") (pinfunction "VIN_VIN") (pintype "bidirectional"))
    )
    (net (code "187") (name "unconnected-(XB1-AD0{slash}DIO0-Pad20)") (class "Default")
      (node (ref "XB1") (pin "20") (pinfunction "AD0/DIO0_20") (pintype "bidirectional"))
    )
    (net (code "188") (name "unconnected-(XB1-AD1{slash}DIO1-Pad19)") (class "Default")
      (node (ref "XB1") (pin "19") (pinfunction "AD1/DIO1_19") (pintype "bidirectional"))
    )
    (net (code "189") (name "unconnected-(XB1-AD2{slash}DIO2-Pad18)") (class "Default")
      (node (ref "XB1") (pin "18") (pinfunction "AD2/DIO2_18") (pintype "bidirectional"))
    )
    (net (code "190") (name "unconnected-(XB1-ASSOC{slash}AD5{slash}DIO5-Pad15)") (class "Default")
      (node (ref "XB1") (pin "15") (pinfunction "ASSOC/AD5/DIO5_15") (pintype "bidirectional"))
    )
    (net (code "191") (name "unconnected-(XB1-CD{slash}DOUT_EN{slash}DO8-Pad4)") (class "Default")
      (node (ref "XB1") (pin "4") (pinfunction "CD/DOUT_EN/DO8_4") (pintype "output"))
    )
    (net (code "192") (name "unconnected-(XB1-COORD_SEL{slash}AD3{slash}DIO3-Pad17)") (class "Default")
      (node (ref "XB1") (pin "17") (pinfunction "COORD_SEL/AD3/DIO3_17") (pintype "bidirectional"))
    )
    (net (code "193") (name "unconnected-(XB1-ON{slash}~{SLEEP}-Pad13)") (class "Default")
      (node (ref "XB1") (pin "13") (pinfunction "ON/~{SLEEP}_13") (pintype "output"))
    )
    (net (code "194") (name "unconnected-(XB1-PWM0{slash}RSSI-Pad6)") (class "Default")
      (node (ref "XB1") (pin "6") (pinfunction "PWM0/RSSI_6") (pintype "output"))
    )
    (net (code "195") (name "unconnected-(XB1-RF_TX{slash}AD4{slash}DIO4-Pad11)") (class "Default")
      (node (ref "XB1") (pin "11") (pinfunction "RF_TX/AD4/DIO4_11") (pintype "bidirectional"))
    )
    (net (code "196") (name "unconnected-(XB1-VREF-Pad14)") (class "Default")
      (node (ref "XB1") (pin "14") (pinfunction "VREF_14") (pintype "input"))
    )
    (net (code "197") (name "unconnected-(XB1-~{CTS}{slash}DIO7-Pad12)") (class "Default")
      (node (ref "XB1") (pin "12") (pinfunction "~{CTS}/DIO7_12") (pintype "bidirectional"))
    )
    (net (code "198") (name "unconnected-(XB1-~{RESET}-Pad5)") (class "Default")
      (node (ref "XB1") (pin "5") (pinfunction "~{RESET}_5") (pintype "input"))
    )
  )
)
